# ProPrj___2026-01-03.net
KiCad netlist of a schematic drawn in EasyEDA Pro
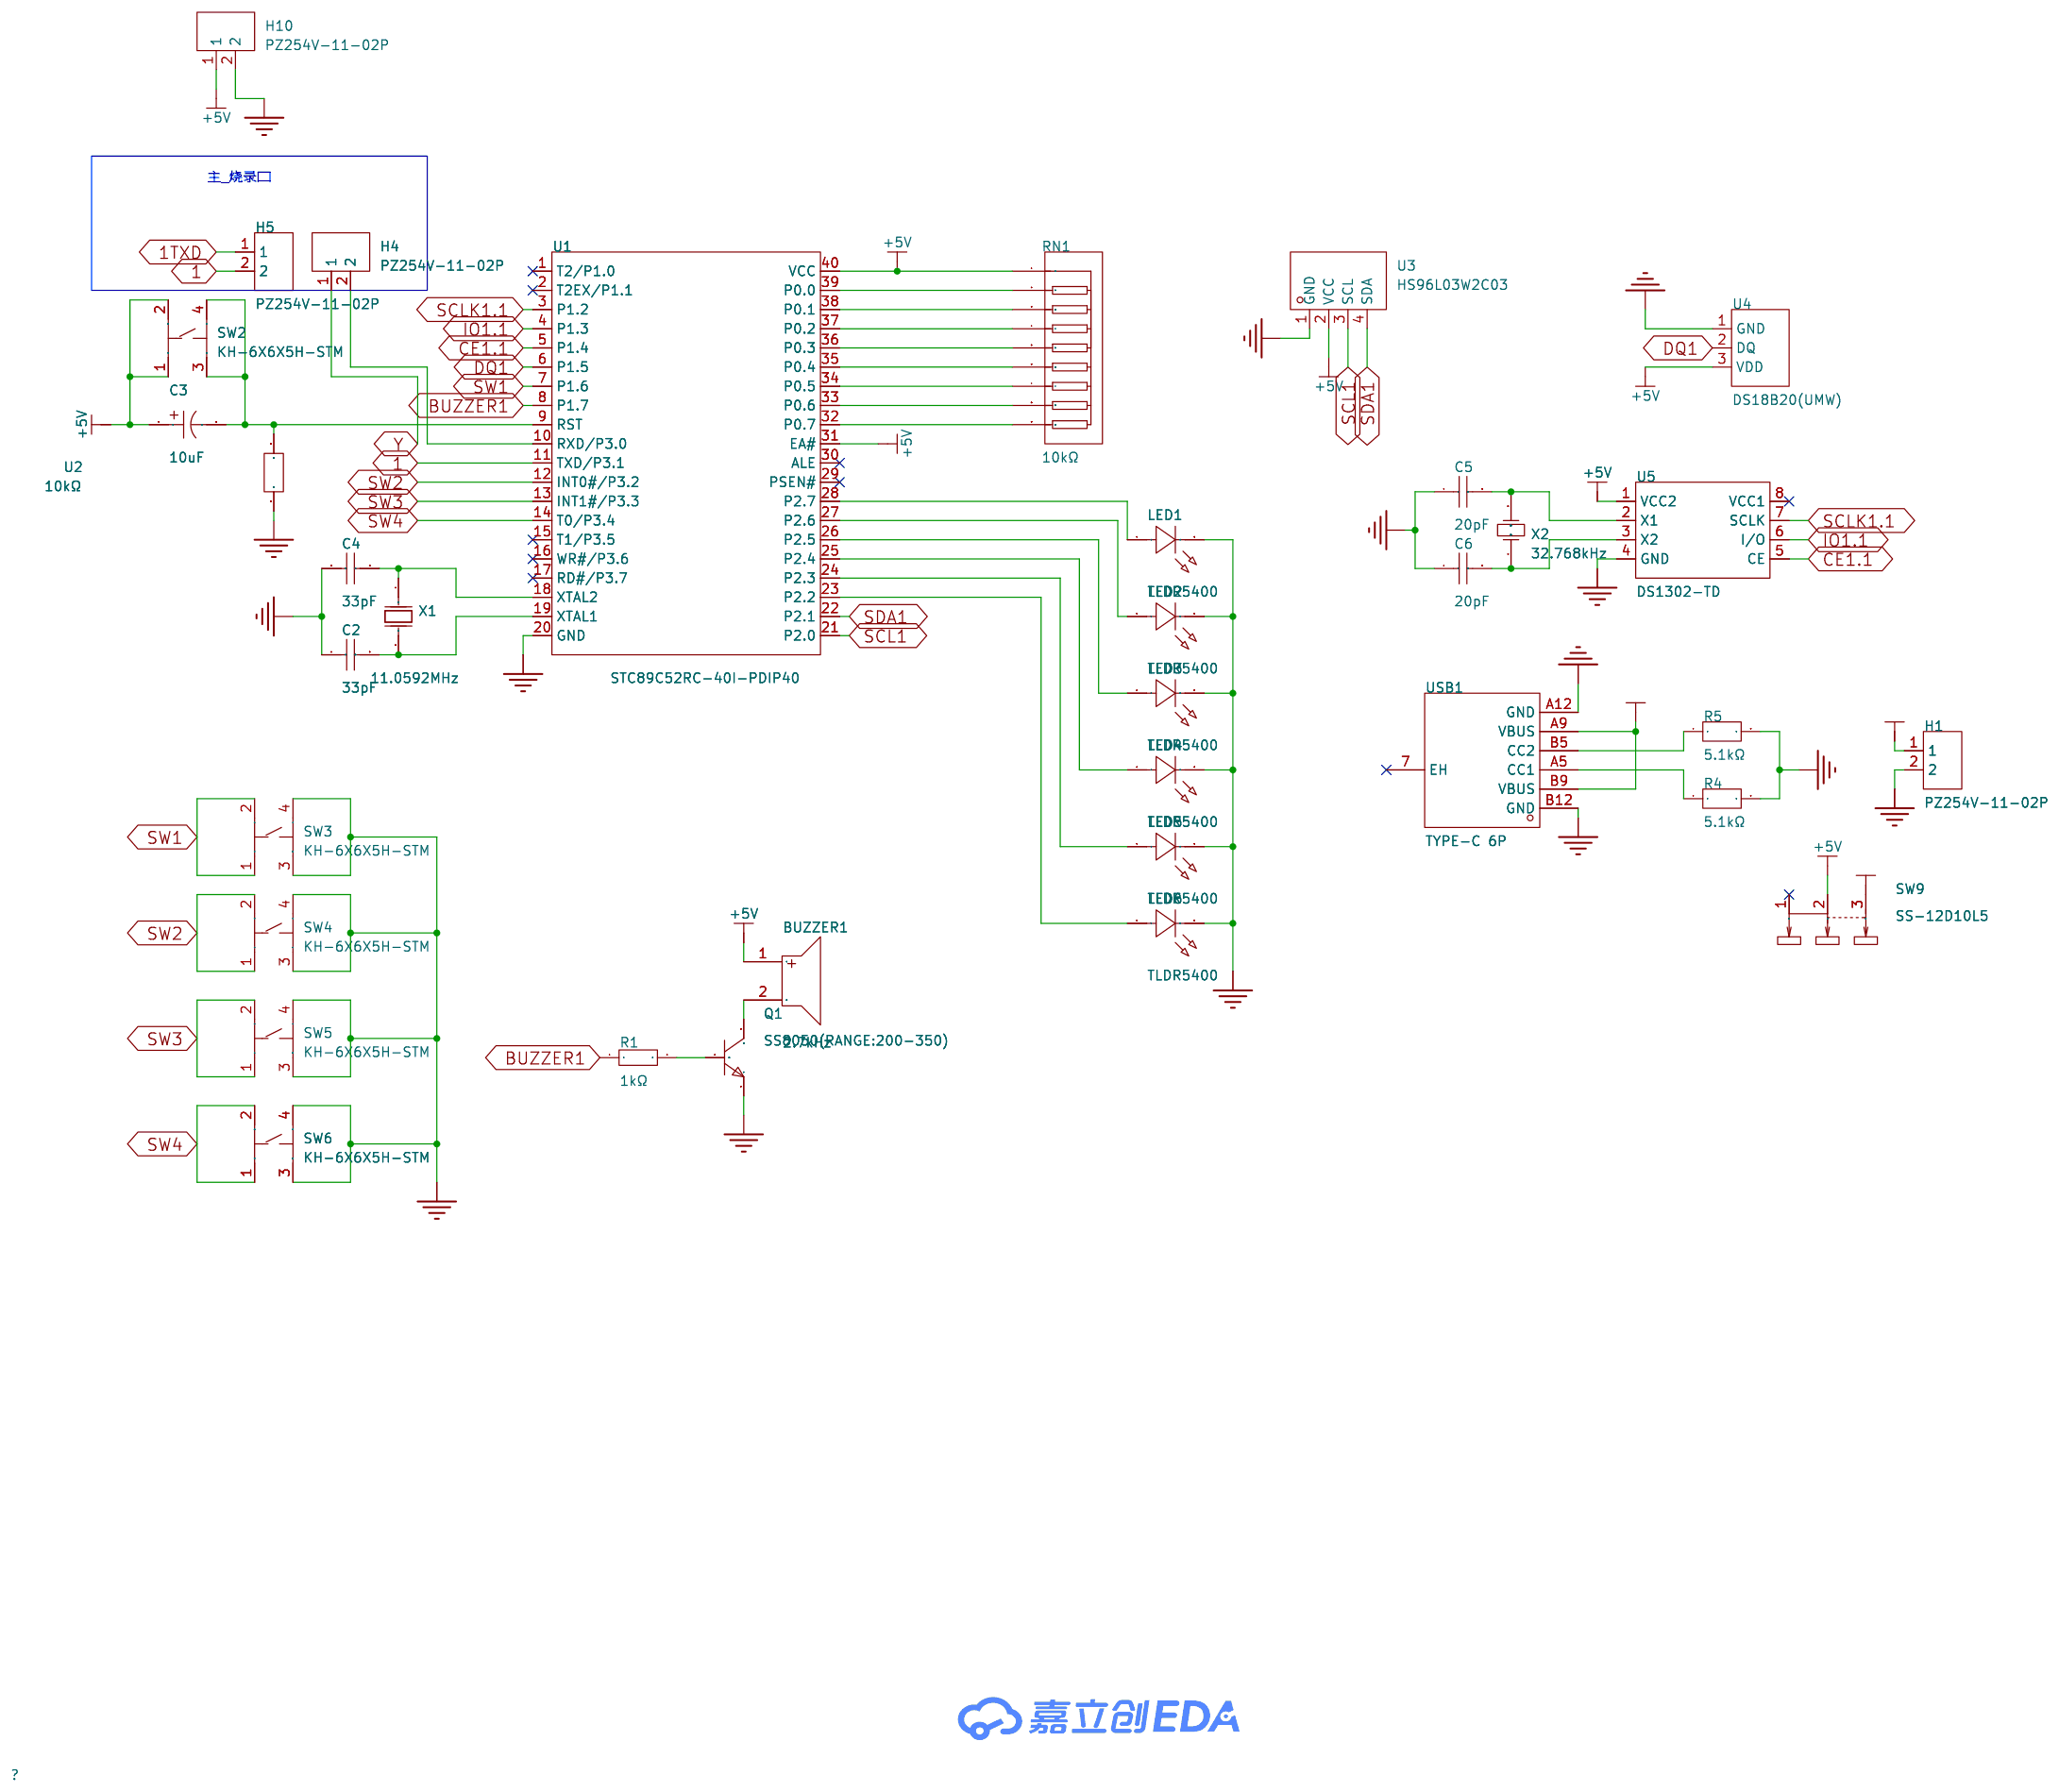
[diagram p0: 主]
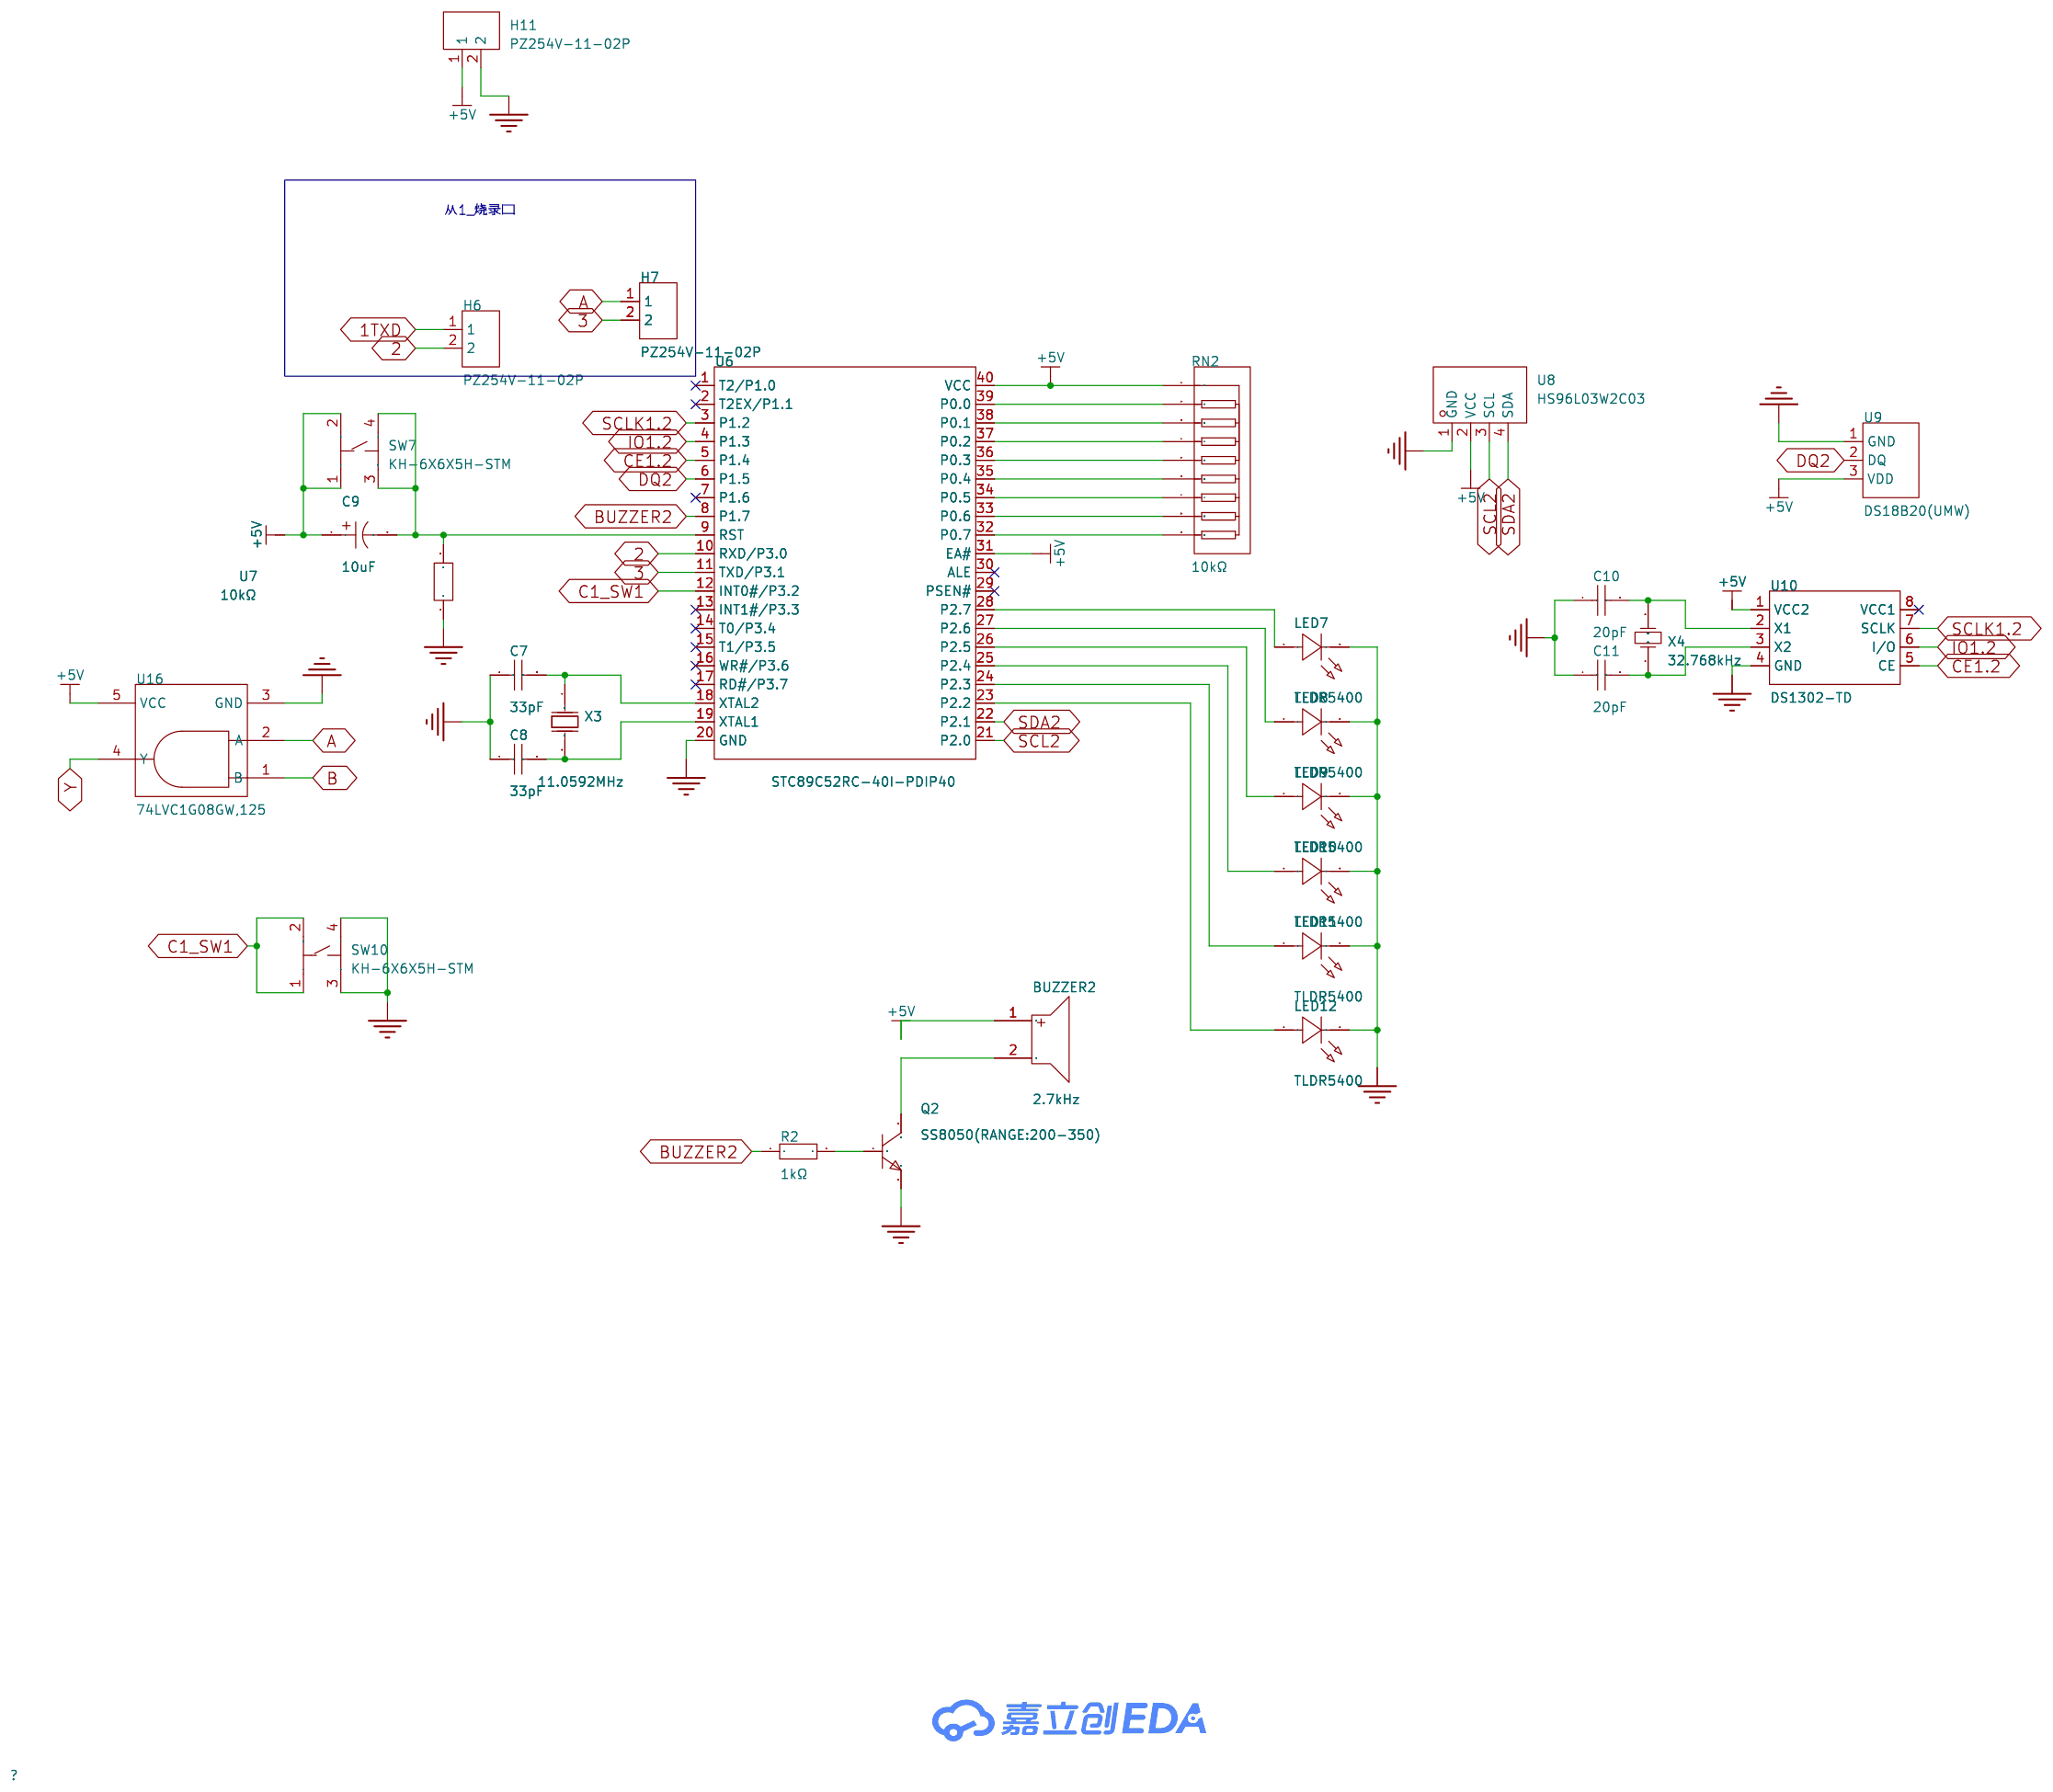
[diagram p1: 从1]
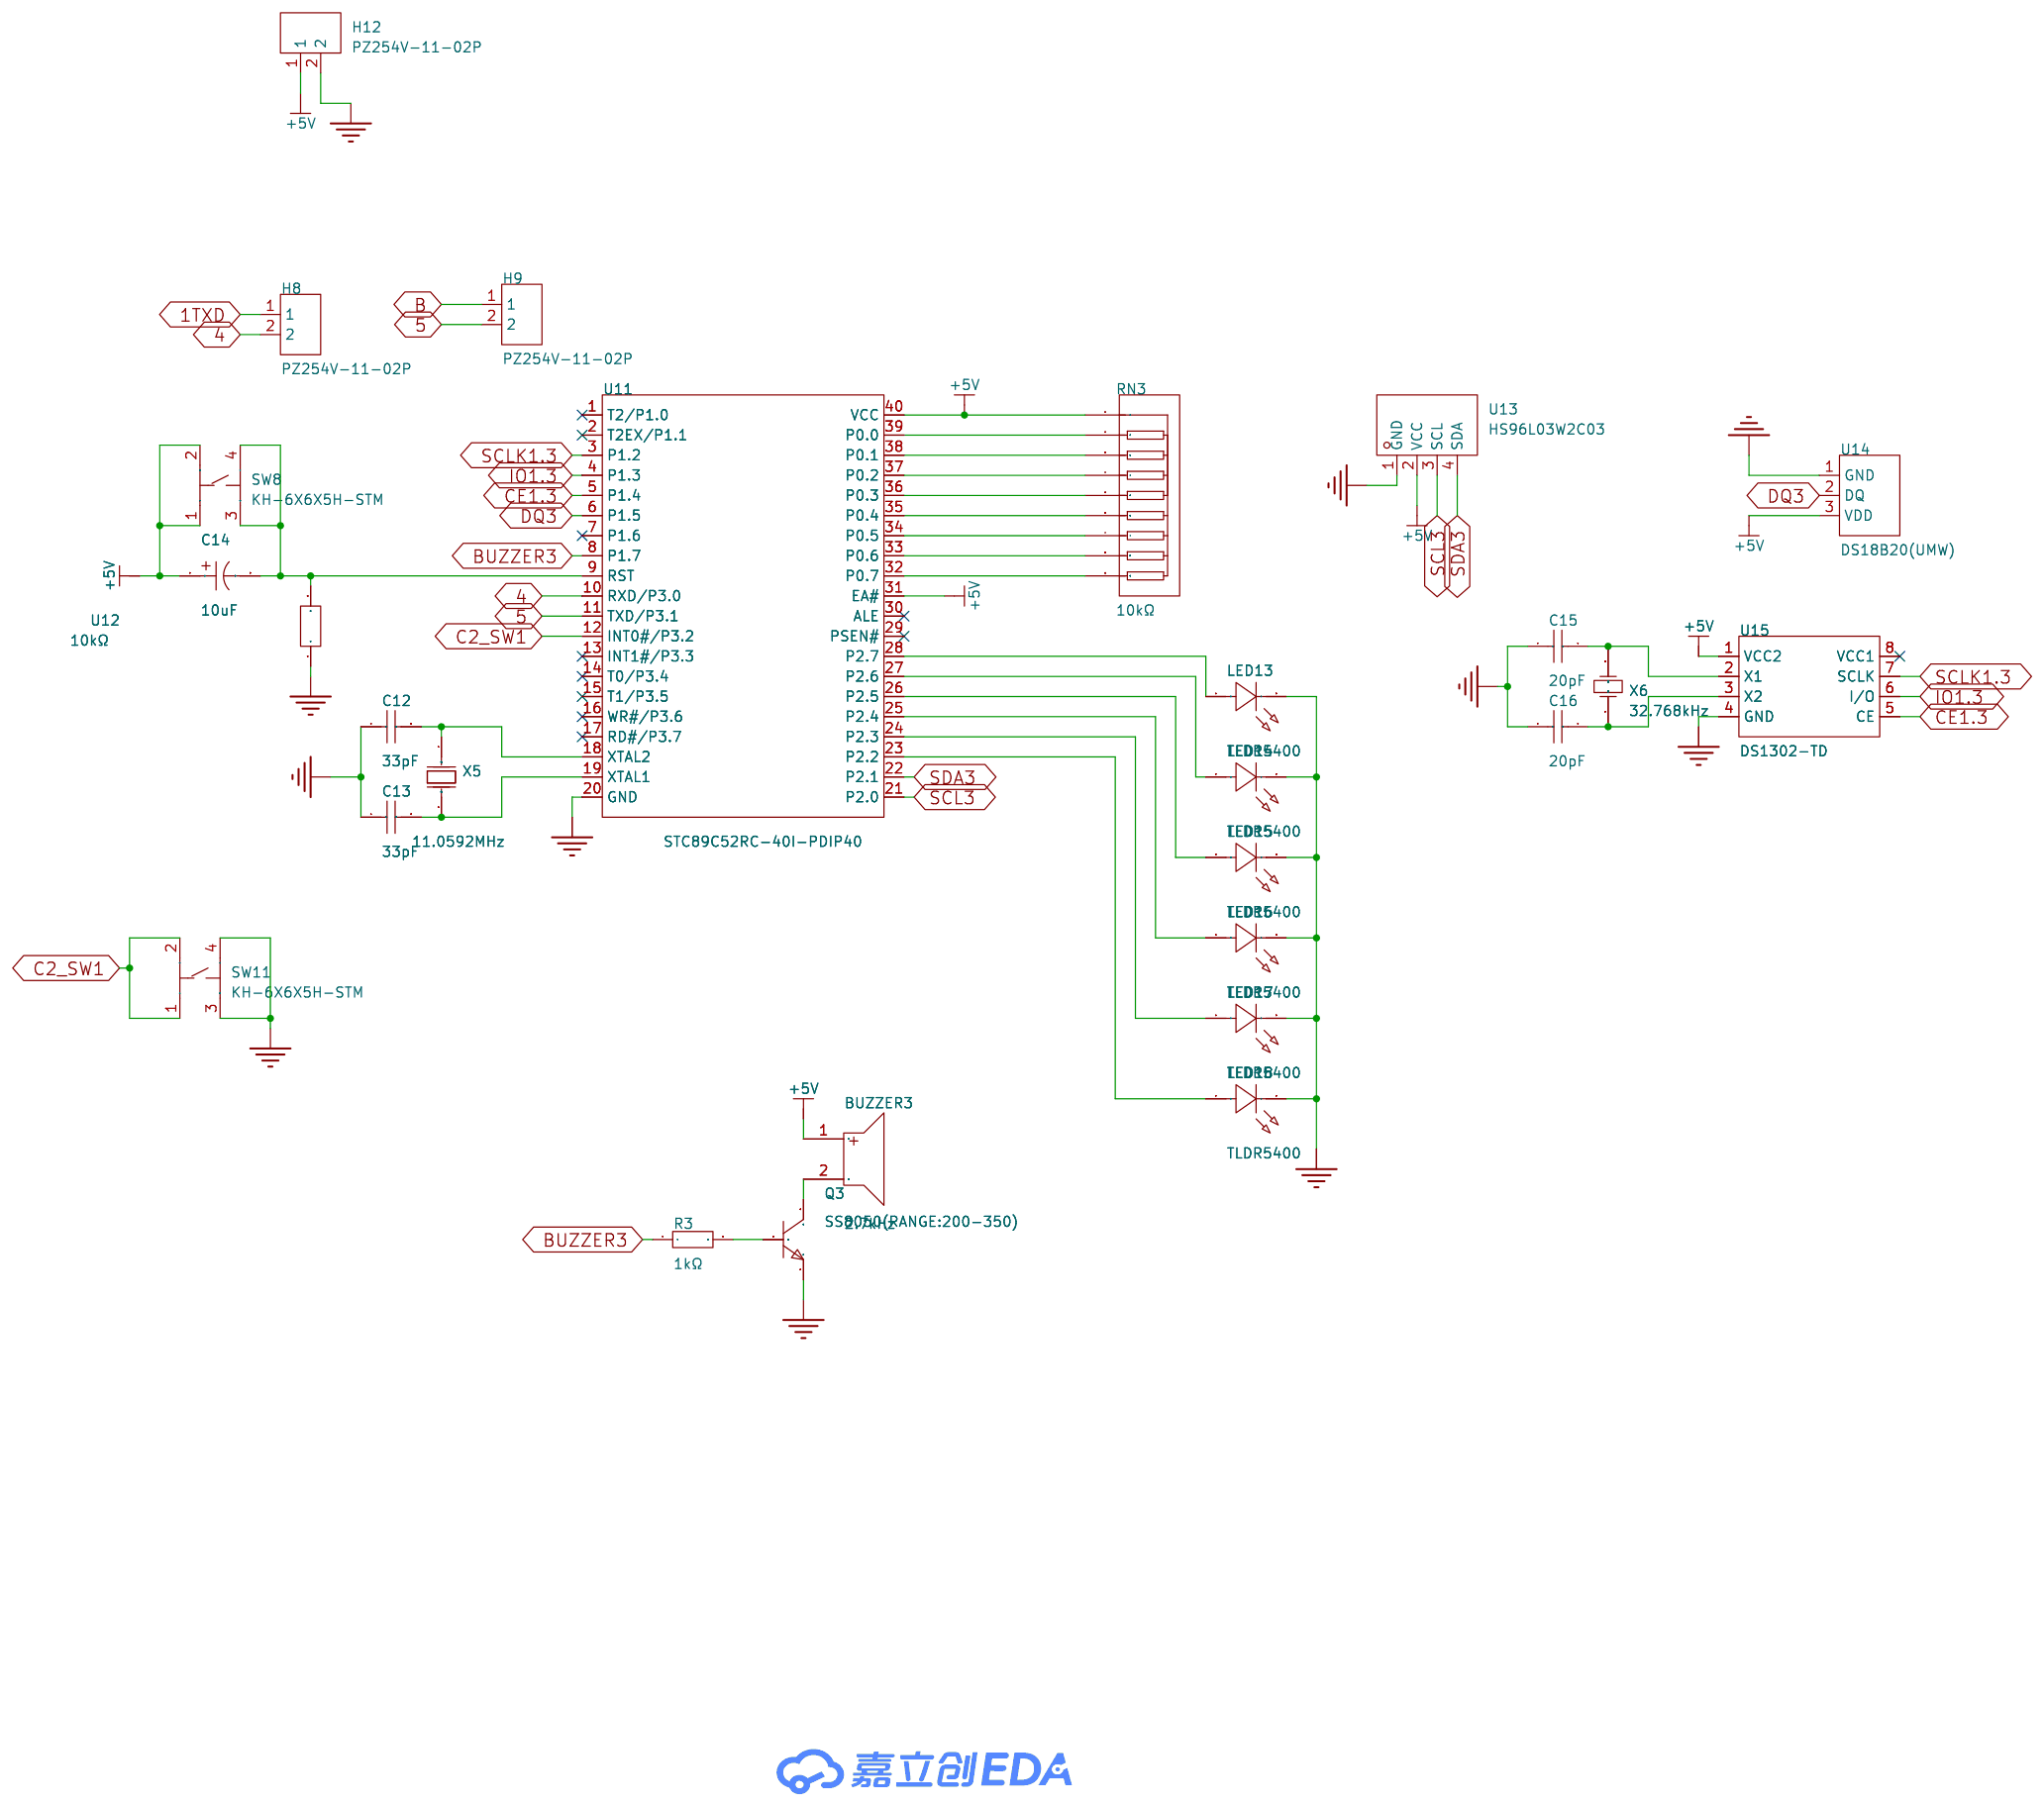
[diagram p2: 从2]

(export (version "E")
  (design (tool "Eeschema 10.0.6"))
  (components
    (comp (ref "BUZZER1")
      (value "2.7kHz")
      (footprint "easyedapro:BUZ-TH_BD9.0-P4.00-D0.6-FD")
      (description "驱动方式:无源(外部驱动);构造类型:电磁式;频率:2.7kHz;声压(SPL):85dB;")
      (fields (field (name "Manufacturer Part") "QMB-09B-03") (field (name "Manufacturer") "华能"))
      (libsource (lib "easyedapro") (part "QMB-09B-03"))
    )
    (comp (ref "C2")
      (value "33pF")
      (footprint "easyedapro:C0603")
      (description "容值:33pF;精度:±5%;额定电压:50V;温度系数:C0G;")
      (fields
        (field (name "Manufacturer Part") "CL10C330JB8NNNC")
        (field (name "Manufacturer") "SAMSUNG(三星)")
      )
      (libsource (lib "easyedapro") (part "CL10C330JB8NNNC"))
    )
    (comp (ref "C3")
      (value "10uF")
      (footprint "easyedapro:CAP-TH_BD10.0-P5.00-D0.6-FD_1")
      (description "容值:10uF;精度:±20%;额定电压:450V;纹波电流:100mA@100kHz;等效串联电阻(ESR):9.45Ω@100kHz;")
      (fields (field (name "Manufacturer Part") "ERG450V10M10x16") (field (name "Manufacturer") "JIERR(捷而瑞)"))
      (libsource (lib "easyedapro") (part "ERG450V10M10X16"))
    )
    (comp (ref "C4")
      (value "33pF")
      (footprint "easyedapro:C0603")
      (description "容值:33pF;精度:±5%;额定电压:50V;温度系数:C0G;")
      (fields
        (field (name "Manufacturer Part") "CL10C330JB8NNNC")
        (field (name "Manufacturer") "SAMSUNG(三星)")
      )
      (libsource (lib "easyedapro") (part "CL10C330JB8NNNC"))
    )
    (comp (ref "C5")
      (value "20pF")
      (footprint "easyedapro:C0603")
      (description "容值:20pF;精度:±5%;额定电压:50V;温度系数:C0G;")
      (fields
        (field (name "Manufacturer Part") "CL10C200JB8NNNC")
        (field (name "Manufacturer") "SAMSUNG(三星)")
      )
      (libsource (lib "easyedapro") (part "CL10C200JB8NNNC"))
    )
    (comp (ref "C6")
      (value "20pF")
      (footprint "easyedapro:C0603")
      (description "容值:20pF;精度:±5%;额定电压:50V;温度系数:C0G;")
      (fields
        (field (name "Manufacturer Part") "CL10C200JB8NNNC")
        (field (name "Manufacturer") "SAMSUNG(三星)")
      )
      (libsource (lib "easyedapro") (part "CL10C200JB8NNNC"))
    )
    (comp (ref "H1")
      (value "PZ254V-11-02P")
      (footprint "easyedapro:HDR-TH_2P-P2.54-V-M")
      (fields (field (name "Manufacturer") "XFCN(兴飞)"))
      (libsource (lib "easyedapro") (part "PZ254V-11-02P"))
    )
    (comp (ref "H4")
      (value "PZ254V-11-02P")
      (footprint "easyedapro:HDR-TH_2P-P2.54-V-M")
      (fields (field (name "Manufacturer") "XFCN(兴飞)"))
      (libsource (lib "easyedapro") (part "PZ254V-11-02P"))
    )
    (comp (ref "H5")
      (value "PZ254V-11-02P")
      (footprint "easyedapro:HDR-TH_2P-P2.54-V-M")
      (fields (field (name "Manufacturer") "XFCN(兴飞)"))
      (libsource (lib "easyedapro") (part "PZ254V-11-02P"))
    )
    (comp (ref "H10")
      (value "PZ254V-11-02P")
      (footprint "easyedapro:HDR-TH_2P-P2.54-V-M")
      (fields (field (name "Manufacturer") "XFCN(兴飞)"))
      (libsource (lib "easyedapro") (part "PZ254V-11-02P"))
    )
    (comp (ref "LED1")
      (value "TLDR5400")
      (footprint "easyedapro:LED-TH_BD5.8-P2.54-FD_RED")
      (fields (field (name "Manufacturer") "VISHAY(威世)"))
      (libsource (lib "easyedapro") (part "TLDR5400"))
    )
    (comp (ref "LED2")
      (value "TLDR5400")
      (footprint "easyedapro:LED-TH_BD5.8-P2.54-FD_RED")
      (fields (field (name "Manufacturer") "VISHAY(威世)"))
      (libsource (lib "easyedapro") (part "TLDR5400"))
    )
    (comp (ref "LED3")
      (value "TLDR5400")
      (footprint "easyedapro:LED-TH_BD5.8-P2.54-FD_RED")
      (fields (field (name "Manufacturer") "VISHAY(威世)"))
      (libsource (lib "easyedapro") (part "TLDR5400"))
    )
    (comp (ref "LED4")
      (value "TLDR5400")
      (footprint "easyedapro:LED-TH_BD5.8-P2.54-FD_RED")
      (fields (field (name "Manufacturer") "VISHAY(威世)"))
      (libsource (lib "easyedapro") (part "TLDR5400"))
    )
    (comp (ref "LED5")
      (value "TLDR5400")
      (footprint "easyedapro:LED-TH_BD5.8-P2.54-FD_RED")
      (fields (field (name "Manufacturer") "VISHAY(威世)"))
      (libsource (lib "easyedapro") (part "TLDR5400"))
    )
    (comp (ref "LED6")
      (value "TLDR5400")
      (footprint "easyedapro:LED-TH_BD5.8-P2.54-FD_RED")
      (fields (field (name "Manufacturer") "VISHAY(威世)"))
      (libsource (lib "easyedapro") (part "TLDR5400"))
    )
    (comp (ref "Q1")
      (value "SS8050(RANGE:200-350)")
      (footprint "easyedapro:SOT-23-3_L2.9-W1.3-P1.90-LS2.4-BR")
      (description "晶体管类型:NPN;集电极电流(Ic):1.5A;集射极击穿电压(Vceo):25V;耗散功率(Pd):300mW;直流电流增益(hFE):200@800mA,1V;")
      (fields (field (name "Manufacturer") "CJ(江苏长电/长晶)"))
      (libsource (lib "easyedapro") (part "SS8050_C2150"))
    )
    (comp (ref "R1")
      (value "1kΩ")
      (footprint "easyedapro:RES-TH_BD2.5-L6.5-P10.50-D0.6")
      (description "电阻类型:金属膜电阻;阻值:1kΩ;精度:±1%;功率:250mW;温度系数:±50ppm/°C;")
      (fields
        (field (name "Manufacturer Part") "MFR0W4F1001A50")
        (field (name "Manufacturer") "UNI-ROYAL(厚声)")
      )
      (libsource (lib "easyedapro") (part "MFR0W4F1001A50"))
    )
    (comp (ref "R4")
      (value "5.1kΩ")
      (footprint "easyedapro:RES-TH_BD2.3-L6.5-P10.50-D0.5")
      (description "电阻类型:金属膜电阻;阻值:5.1kΩ;精度:±1%;功率:250mW;温度系数:±200ppm/°C;")
      (fields (field (name "Manufacturer Part") "MF1/4W-5.1KΩ±1%T52") (field (name "Manufacturer") "华星机电"))
      (libsource (lib "easyedapro") (part "MF1/4W-5.1KΩ±1%T52"))
    )
    (comp (ref "R5")
      (value "5.1kΩ")
      (footprint "easyedapro:RES-TH_BD2.3-L6.5-P10.50-D0.5")
      (description "电阻类型:金属膜电阻;阻值:5.1kΩ;精度:±1%;功率:250mW;温度系数:±200ppm/°C;")
      (fields (field (name "Manufacturer Part") "MF1/4W-5.1KΩ±1%T52") (field (name "Manufacturer") "华星机电"))
      (libsource (lib "easyedapro") (part "MF1/4W-5.1KΩ±1%T52"))
    )
    (comp (ref "RN1")
      (value "10kΩ")
      (footprint "easyedapro:RES-ARRAY-TH_9P-P2.54-D1.0")
      (description "电阻器数:8;阻值:10kΩ;精度:±5%;单个元件功率:125mW;温度系数:±100ppm/°C;")
      (fields (field (name "Manufacturer Part") "A09-103JP") (field (name "Manufacturer") "FH(风华)"))
      (libsource (lib "easyedapro") (part "A09-103JP"))
    )
    (comp (ref "SW2")
      (value "KH-6X6X5H-STM")
      (footprint "easyedapro:SW-SMD_4P-L6.0-W6.0-P4.50-LS9.0_H5.0")
      (description "电路结构:单刀单掷;按钮形状:圆形按钮;安装方式:立贴;开关长度:6mm;开关宽度:6mm;开关高度:5mm;带支架:不带支架;触点电流:50mA;额定电压:12V;工作寿命:8万次;")
      (fields (field (name "Manufacturer") "kinghelm(金航标)"))
      (libsource (lib "easyedapro") (part "KH-6X6X5H-STM"))
    )
    (comp (ref "SW3")
      (value "KH-6X6X5H-STM")
      (footprint "easyedapro:SW-SMD_4P-L6.0-W6.0-P4.50-LS9.0_H5.0")
      (description "电路结构:单刀单掷;按钮形状:圆形按钮;安装方式:立贴;开关长度:6mm;开关宽度:6mm;开关高度:5mm;带支架:不带支架;触点电流:50mA;额定电压:12V;工作寿命:8万次;")
      (fields (field (name "Manufacturer") "kinghelm(金航标)"))
      (libsource (lib "easyedapro") (part "KH-6X6X5H-STM"))
    )
    (comp (ref "SW4")
      (value "KH-6X6X5H-STM")
      (footprint "easyedapro:SW-SMD_4P-L6.0-W6.0-P4.50-LS9.0_H5.0")
      (description "电路结构:单刀单掷;按钮形状:圆形按钮;安装方式:立贴;开关长度:6mm;开关宽度:6mm;开关高度:5mm;带支架:不带支架;触点电流:50mA;额定电压:12V;工作寿命:8万次;")
      (fields (field (name "Manufacturer") "kinghelm(金航标)"))
      (libsource (lib "easyedapro") (part "KH-6X6X5H-STM"))
    )
    (comp (ref "SW5")
      (value "KH-6X6X5H-STM")
      (footprint "easyedapro:SW-SMD_4P-L6.0-W6.0-P4.50-LS9.0_H5.0")
      (description "电路结构:单刀单掷;按钮形状:圆形按钮;安装方式:立贴;开关长度:6mm;开关宽度:6mm;开关高度:5mm;带支架:不带支架;触点电流:50mA;额定电压:12V;工作寿命:8万次;")
      (fields (field (name "Manufacturer") "kinghelm(金航标)"))
      (libsource (lib "easyedapro") (part "KH-6X6X5H-STM"))
    )
    (comp (ref "SW6")
      (value "KH-6X6X5H-STM")
      (footprint "easyedapro:SW-SMD_4P-L6.0-W6.0-P4.50-LS9.0_H5.0")
      (description "电路结构:单刀单掷;按钮形状:圆形按钮;安装方式:立贴;开关长度:6mm;开关宽度:6mm;开关高度:5mm;带支架:不带支架;触点电流:50mA;额定电压:12V;工作寿命:8万次;")
      (fields (field (name "Manufacturer") "kinghelm(金航标)"))
      (libsource (lib "easyedapro") (part "KH-6X6X5H-STM"))
    )
    (comp (ref "SW9")
      (value "SS-12D10L5")
      (footprint "easyedapro:SW-TH_SS-12D10L5")
      (description "电路结构:单刀双掷;安装方式:直插;开关颜色:黑色;额定电流:3A;额定电压:125V;工作寿命:1万次;")
      (fields (field (name "Manufacturer") "XKB Connection(中国星坤)"))
      (libsource (lib "easyedapro") (part "SS-12D10L5"))
    )
    (comp (ref "U1")
      (value "STC89C52RC-40I-PDIP40")
      (footprint "easyedapro:DIP-40_L52.0-W13.7-P2.54-LS15.2-BL")
      (description "CPU内核:51家族;CPU最大主频:-;")
      (fields (field (name "Manufacturer") "STC"))
      (libsource (lib "easyedapro") (part "STC89C52RC-40I"))
    )
    (comp (ref "U2")
      (value "10kΩ")
      (footprint "easyedapro:RES-TH_BD2.3-L6.3-P10.30-D0.6")
      (description "电阻类型:金属膜电阻;阻值:10kΩ;精度:±1%;功率:600mW;温度系数:±50ppm/°C;")
      (fields
        (field (name "Manufacturer Part") "LR1F10K")
        (field (name "Manufacturer") "TE Connectivity(泰科电子)")
      )
      (libsource (lib "easyedapro") (part "LR1F10K"))
    )
    (comp (ref "U3")
      (value "HS96L03W2C03")
      (footprint "easyedapro:OLED-TH_L27.8-W27.2-P2.54_C9900033791")
      (description "主控芯片:SSD1315;接口类型:I2C;尺寸(inch):0.96;像素分辨率:128x64;")
      (fields (field (name "Manufacturer") "HS(汉昇)"))
      (libsource (lib "easyedapro") (part "HS96L03W2C03"))
    )
    (comp (ref "U4")
      (value "DS18B20(UMW)")
      (footprint "easyedapro:TO-92-3_L4.9-W3.7-P1.27-L")
      (description "温度范围:-55°C~+125°C;精度:±0.4°C;接口类型:-;")
      (fields (field (name "Manufacturer") "UMW(友台半导体)"))
      (libsource (lib "easyedapro") (part "DS18B20"))
    )
    (comp (ref "U5")
      (value "DS1302-TD")
      (footprint "easyedapro:SOP-8_L4.9-W3.9-P1.27-LS6.0-BL")
      (description "接口类型:SPI;晶振:外置;闹钟输出:有;")
      (fields (field (name "Manufacturer") "TDSEMIC(拓电半导体)"))
      (libsource (lib "easyedapro") (part "DS1302-TD"))
    )
    (comp (ref "USB1")
      (value "TYPE-C 6P")
      (footprint "easyedapro:TYPE-C-SMD_TYPE-C-6P")
      (description "连接器类型:Type-C;标准:USB 3.1;公母:母;安装方式:卧贴;触点数量:6P;端口数量:1;额定电流 - 电源:5A;工作温度范围:-40°C~+85°C;")
      (fields (field (name "Manufacturer") "SHOU HAN(首韩)"))
      (libsource (lib "easyedapro") (part "TYPE-C 6P"))
    )
    (comp (ref "X1")
      (value "11.0592MHz")
      (footprint "easyedapro:HC-49US_L11.5-W4.5-P4.88")
      (description "晶振类型:直插晶振;频率:11.0592MHz;常温频差:±20ppm;负载电容:20pF;频率稳定度:±30ppm;")
      (fields
        (field (name "Manufacturer Part") "X49SD110592MSD2SC")
        (field (name "Manufacturer") "YXC(扬兴晶振)")
      )
      (libsource (lib "easyedapro") (part "X49SD110592MSD2SC"))
    )
    (comp (ref "X2")
      (value "32.768kHz")
      (footprint "easyedapro:OSC-TH_BD3.1-P0.8-D0.3")
      (description "晶振类型:直插晶振;频率:32.768kHz;常温频差:±10ppm;负载电容:12.5pF;频率稳定度:±20ppm;")
      (fields (field (name "Manufacturer Part") "X308032768KGB2SC") (field (name "Manufacturer") "YXC(扬兴晶振)"))
      (libsource (lib "easyedapro") (part "X308032768KGB2SC"))
    )
    (comp (ref "BUZZER2")
      (value "2.7kHz")
      (footprint "easyedapro:BUZ-TH_BD9.0-P4.00-D0.6-FD")
      (description "驱动方式:无源(外部驱动);构造类型:电磁式;频率:2.7kHz;声压(SPL):85dB;")
      (fields (field (name "Manufacturer Part") "QMB-09B-03") (field (name "Manufacturer") "华能"))
      (libsource (lib "easyedapro") (part "QMB-09B-03"))
    )
    (comp (ref "C7")
      (value "33pF")
      (footprint "easyedapro:C0603")
      (description "容值:33pF;精度:±5%;额定电压:50V;温度系数:C0G;")
      (fields
        (field (name "Manufacturer Part") "CL10C330JB8NNNC")
        (field (name "Manufacturer") "SAMSUNG(三星)")
      )
      (libsource (lib "easyedapro") (part "CL10C330JB8NNNC"))
    )
    (comp (ref "C8")
      (value "33pF")
      (footprint "easyedapro:C0603")
      (description "容值:33pF;精度:±5%;额定电压:50V;温度系数:C0G;")
      (fields
        (field (name "Manufacturer Part") "CL10C330JB8NNNC")
        (field (name "Manufacturer") "SAMSUNG(三星)")
      )
      (libsource (lib "easyedapro") (part "CL10C330JB8NNNC"))
    )
    (comp (ref "C9")
      (value "10uF")
      (footprint "easyedapro:CAP-TH_BD10.0-P5.00-D0.6-FD_1")
      (description "容值:10uF;精度:±20%;额定电压:450V;纹波电流:100mA@100kHz;等效串联电阻(ESR):9.45Ω@100kHz;")
      (fields (field (name "Manufacturer Part") "ERG450V10M10x16") (field (name "Manufacturer") "JIERR(捷而瑞)"))
      (libsource (lib "easyedapro") (part "ERG450V10M10X16"))
    )
    (comp (ref "C10")
      (value "20pF")
      (footprint "easyedapro:C0603")
      (description "容值:20pF;精度:±5%;额定电压:50V;温度系数:C0G;")
      (fields
        (field (name "Manufacturer Part") "CL10C200JB8NNNC")
        (field (name "Manufacturer") "SAMSUNG(三星)")
      )
      (libsource (lib "easyedapro") (part "CL10C200JB8NNNC"))
    )
    (comp (ref "C11")
      (value "20pF")
      (footprint "easyedapro:C0603")
      (description "容值:20pF;精度:±5%;额定电压:50V;温度系数:C0G;")
      (fields
        (field (name "Manufacturer Part") "CL10C200JB8NNNC")
        (field (name "Manufacturer") "SAMSUNG(三星)")
      )
      (libsource (lib "easyedapro") (part "CL10C200JB8NNNC"))
    )
    (comp (ref "H6")
      (value "PZ254V-11-02P")
      (footprint "easyedapro:HDR-TH_2P-P2.54-V-M")
      (fields (field (name "Manufacturer") "XFCN(兴飞)"))
      (libsource (lib "easyedapro") (part "PZ254V-11-02P"))
    )
    (comp (ref "H7")
      (value "PZ254V-11-02P")
      (footprint "easyedapro:HDR-TH_2P-P2.54-V-M")
      (fields (field (name "Manufacturer") "XFCN(兴飞)"))
      (libsource (lib "easyedapro") (part "PZ254V-11-02P"))
    )
    (comp (ref "H11")
      (value "PZ254V-11-02P")
      (footprint "easyedapro:HDR-TH_2P-P2.54-V-M")
      (fields (field (name "Manufacturer") "XFCN(兴飞)"))
      (libsource (lib "easyedapro") (part "PZ254V-11-02P"))
    )
    (comp (ref "LED7")
      (value "TLDR5400")
      (footprint "easyedapro:LED-TH_BD5.8-P2.54-FD_RED")
      (fields (field (name "Manufacturer") "VISHAY(威世)"))
      (libsource (lib "easyedapro") (part "TLDR5400"))
    )
    (comp (ref "LED8")
      (value "TLDR5400")
      (footprint "easyedapro:LED-TH_BD5.8-P2.54-FD_RED")
      (fields (field (name "Manufacturer") "VISHAY(威世)"))
      (libsource (lib "easyedapro") (part "TLDR5400"))
    )
    (comp (ref "LED9")
      (value "TLDR5400")
      (footprint "easyedapro:LED-TH_BD5.8-P2.54-FD_RED")
      (fields (field (name "Manufacturer") "VISHAY(威世)"))
      (libsource (lib "easyedapro") (part "TLDR5400"))
    )
    (comp (ref "LED10")
      (value "TLDR5400")
      (footprint "easyedapro:LED-TH_BD5.8-P2.54-FD_RED")
      (fields (field (name "Manufacturer") "VISHAY(威世)"))
      (libsource (lib "easyedapro") (part "TLDR5400"))
    )
    (comp (ref "LED11")
      (value "TLDR5400")
      (footprint "easyedapro:LED-TH_BD5.8-P2.54-FD_RED")
      (fields (field (name "Manufacturer") "VISHAY(威世)"))
      (libsource (lib "easyedapro") (part "TLDR5400"))
    )
    (comp (ref "LED12")
      (value "TLDR5400")
      (footprint "easyedapro:LED-TH_BD5.8-P2.54-FD_RED")
      (fields (field (name "Manufacturer") "VISHAY(威世)"))
      (libsource (lib "easyedapro") (part "TLDR5400"))
    )
    (comp (ref "Q2")
      (value "SS8050(RANGE:200-350)")
      (footprint "easyedapro:SOT-23-3_L2.9-W1.3-P1.90-LS2.4-BR")
      (description "晶体管类型:NPN;集电极电流(Ic):1.5A;集射极击穿电压(Vceo):25V;耗散功率(Pd):300mW;直流电流增益(hFE):200@800mA,1V;")
      (fields (field (name "Manufacturer") "CJ(江苏长电/长晶)"))
      (libsource (lib "easyedapro") (part "SS8050_C2150"))
    )
    (comp (ref "R2")
      (value "1kΩ")
      (footprint "easyedapro:RES-TH_BD2.5-L6.5-P10.50-D0.6")
      (description "电阻类型:金属膜电阻;阻值:1kΩ;精度:±1%;功率:250mW;温度系数:±50ppm/°C;")
      (fields
        (field (name "Manufacturer Part") "MFR0W4F1001A50")
        (field (name "Manufacturer") "UNI-ROYAL(厚声)")
      )
      (libsource (lib "easyedapro") (part "MFR0W4F1001A50"))
    )
    (comp (ref "RN2")
      (value "10kΩ")
      (footprint "easyedapro:RES-ARRAY-TH_9P-P2.54-D1.0")
      (description "电阻器数:8;阻值:10kΩ;精度:±5%;单个元件功率:125mW;温度系数:±100ppm/°C;")
      (fields (field (name "Manufacturer Part") "A09-103JP") (field (name "Manufacturer") "FH(风华)"))
      (libsource (lib "easyedapro") (part "A09-103JP"))
    )
    (comp (ref "SW7")
      (value "KH-6X6X5H-STM")
      (footprint "easyedapro:SW-SMD_4P-L6.0-W6.0-P4.50-LS9.0_H5.0")
      (description "电路结构:单刀单掷;按钮形状:圆形按钮;安装方式:立贴;开关长度:6mm;开关宽度:6mm;开关高度:5mm;带支架:不带支架;触点电流:50mA;额定电压:12V;工作寿命:8万次;")
      (fields (field (name "Manufacturer") "kinghelm(金航标)"))
      (libsource (lib "easyedapro") (part "KH-6X6X5H-STM"))
    )
    (comp (ref "SW10")
      (value "KH-6X6X5H-STM")
      (footprint "easyedapro:SW-SMD_4P-L6.0-W6.0-P4.50-LS9.0_H5.0")
      (description "电路结构:单刀单掷;按钮形状:圆形按钮;安装方式:立贴;开关长度:6mm;开关宽度:6mm;开关高度:5mm;带支架:不带支架;触点电流:50mA;额定电压:12V;工作寿命:8万次;")
      (fields (field (name "Manufacturer") "kinghelm(金航标)"))
      (libsource (lib "easyedapro") (part "KH-6X6X5H-STM"))
    )
    (comp (ref "U6")
      (value "STC89C52RC-40I-PDIP40")
      (footprint "easyedapro:DIP-40_L52.0-W13.7-P2.54-LS15.2-BL")
      (description "CPU内核:51家族;CPU最大主频:-;")
      (fields (field (name "Manufacturer") "STC"))
      (libsource (lib "easyedapro") (part "STC89C52RC-40I"))
    )
    (comp (ref "U7")
      (value "10kΩ")
      (footprint "easyedapro:RES-TH_BD2.3-L6.3-P10.30-D0.6")
      (description "电阻类型:金属膜电阻;阻值:10kΩ;精度:±1%;功率:600mW;温度系数:±50ppm/°C;")
      (fields
        (field (name "Manufacturer Part") "LR1F10K")
        (field (name "Manufacturer") "TE Connectivity(泰科电子)")
      )
      (libsource (lib "easyedapro") (part "LR1F10K"))
    )
    (comp (ref "U8")
      (value "HS96L03W2C03")
      (footprint "easyedapro:OLED-TH_L27.8-W27.2-P2.54_C9900033791")
      (description "主控芯片:SSD1315;接口类型:I2C;尺寸(inch):0.96;像素分辨率:128x64;")
      (fields (field (name "Manufacturer") "HS(汉昇)"))
      (libsource (lib "easyedapro") (part "HS96L03W2C03"))
    )
    (comp (ref "U9")
      (value "DS18B20(UMW)")
      (footprint "easyedapro:TO-92-3_L4.9-W3.7-P1.27-L")
      (description "温度范围:-55°C~+125°C;精度:±0.4°C;接口类型:-;")
      (fields (field (name "Manufacturer") "UMW(友台半导体)"))
      (libsource (lib "easyedapro") (part "DS18B20"))
    )
    (comp (ref "U10")
      (value "DS1302-TD")
      (footprint "easyedapro:SOP-8_L4.9-W3.9-P1.27-LS6.0-BL")
      (description "接口类型:SPI;晶振:外置;闹钟输出:有;")
      (fields (field (name "Manufacturer") "TDSEMIC(拓电半导体)"))
      (libsource (lib "easyedapro") (part "DS1302-TD"))
    )
    (comp (ref "U16")
      (value "74LVC1G08GW,125")
      (footprint "easyedapro:SOT-353_L2.1-W1.3-P0.65-LS2.3-BR")
      (description "逻辑类型:与门;通道数:1;电源电压:1.65V~5.5V;静态电流(最大值):4uA;最大传播延迟:4ns@5V,50pF;")
      (fields (field (name "Manufacturer") "Nexperia(安世)"))
      (libsource (lib "easyedapro") (part "74LVC1G08GW,125"))
    )
    (comp (ref "X3")
      (value "11.0592MHz")
      (footprint "easyedapro:HC-49US_L11.5-W4.5-P4.88")
      (description "晶振类型:直插晶振;频率:11.0592MHz;常温频差:±20ppm;负载电容:20pF;频率稳定度:±30ppm;")
      (fields
        (field (name "Manufacturer Part") "X49SD110592MSD2SC")
        (field (name "Manufacturer") "YXC(扬兴晶振)")
      )
      (libsource (lib "easyedapro") (part "X49SD110592MSD2SC"))
    )
    (comp (ref "X4")
      (value "32.768kHz")
      (footprint "easyedapro:OSC-TH_BD3.1-P0.8-D0.3")
      (description "晶振类型:直插晶振;频率:32.768kHz;常温频差:±10ppm;负载电容:12.5pF;频率稳定度:±20ppm;")
      (fields (field (name "Manufacturer Part") "X308032768KGB2SC") (field (name "Manufacturer") "YXC(扬兴晶振)"))
      (libsource (lib "easyedapro") (part "X308032768KGB2SC"))
    )
    (comp (ref "BUZZER3")
      (value "2.7kHz")
      (footprint "easyedapro:BUZ-TH_BD9.0-P4.00-D0.6-FD")
      (description "驱动方式:无源(外部驱动);构造类型:电磁式;频率:2.7kHz;声压(SPL):85dB;")
      (fields (field (name "Manufacturer Part") "QMB-09B-03") (field (name "Manufacturer") "华能"))
      (libsource (lib "easyedapro") (part "QMB-09B-03"))
    )
    (comp (ref "C12")
      (value "33pF")
      (footprint "easyedapro:C0603")
      (description "容值:33pF;精度:±5%;额定电压:50V;温度系数:C0G;")
      (fields
        (field (name "Manufacturer Part") "CL10C330JB8NNNC")
        (field (name "Manufacturer") "SAMSUNG(三星)")
      )
      (libsource (lib "easyedapro") (part "CL10C330JB8NNNC"))
    )
    (comp (ref "C13")
      (value "33pF")
      (footprint "easyedapro:C0603")
      (description "容值:33pF;精度:±5%;额定电压:50V;温度系数:C0G;")
      (fields
        (field (name "Manufacturer Part") "CL10C330JB8NNNC")
        (field (name "Manufacturer") "SAMSUNG(三星)")
      )
      (libsource (lib "easyedapro") (part "CL10C330JB8NNNC"))
    )
    (comp (ref "C14")
      (value "10uF")
      (footprint "easyedapro:CAP-TH_BD10.0-P5.00-D0.6-FD_1")
      (description "容值:10uF;精度:±20%;额定电压:450V;纹波电流:100mA@100kHz;等效串联电阻(ESR):9.45Ω@100kHz;")
      (fields (field (name "Manufacturer Part") "ERG450V10M10x16") (field (name "Manufacturer") "JIERR(捷而瑞)"))
      (libsource (lib "easyedapro") (part "ERG450V10M10X16"))
    )
    (comp (ref "C15")
      (value "20pF")
      (footprint "easyedapro:C0603")
      (description "容值:20pF;精度:±5%;额定电压:50V;温度系数:C0G;")
      (fields
        (field (name "Manufacturer Part") "CL10C200JB8NNNC")
        (field (name "Manufacturer") "SAMSUNG(三星)")
      )
      (libsource (lib "easyedapro") (part "CL10C200JB8NNNC"))
    )
    (comp (ref "C16")
      (value "20pF")
      (footprint "easyedapro:C0603")
      (description "容值:20pF;精度:±5%;额定电压:50V;温度系数:C0G;")
      (fields
        (field (name "Manufacturer Part") "CL10C200JB8NNNC")
        (field (name "Manufacturer") "SAMSUNG(三星)")
      )
      (libsource (lib "easyedapro") (part "CL10C200JB8NNNC"))
    )
    (comp (ref "H8")
      (value "PZ254V-11-02P")
      (footprint "easyedapro:HDR-TH_2P-P2.54-V-M")
      (fields (field (name "Manufacturer") "XFCN(兴飞)"))
      (libsource (lib "easyedapro") (part "PZ254V-11-02P"))
    )
    (comp (ref "H9")
      (value "PZ254V-11-02P")
      (footprint "easyedapro:HDR-TH_2P-P2.54-V-M")
      (fields (field (name "Manufacturer") "XFCN(兴飞)"))
      (libsource (lib "easyedapro") (part "PZ254V-11-02P"))
    )
    (comp (ref "H12")
      (value "PZ254V-11-02P")
      (footprint "easyedapro:HDR-TH_2P-P2.54-V-M")
      (fields (field (name "Manufacturer") "XFCN(兴飞)"))
      (libsource (lib "easyedapro") (part "PZ254V-11-02P"))
    )
    (comp (ref "LED13")
      (value "TLDR5400")
      (footprint "easyedapro:LED-TH_BD5.8-P2.54-FD_RED")
      (fields (field (name "Manufacturer") "VISHAY(威世)"))
      (libsource (lib "easyedapro") (part "TLDR5400"))
    )
    (comp (ref "LED14")
      (value "TLDR5400")
      (footprint "easyedapro:LED-TH_BD5.8-P2.54-FD_RED")
      (fields (field (name "Manufacturer") "VISHAY(威世)"))
      (libsource (lib "easyedapro") (part "TLDR5400"))
    )
    (comp (ref "LED15")
      (value "TLDR5400")
      (footprint "easyedapro:LED-TH_BD5.8-P2.54-FD_RED")
      (fields (field (name "Manufacturer") "VISHAY(威世)"))
      (libsource (lib "easyedapro") (part "TLDR5400"))
    )
    (comp (ref "LED16")
      (value "TLDR5400")
      (footprint "easyedapro:LED-TH_BD5.8-P2.54-FD_RED")
      (fields (field (name "Manufacturer") "VISHAY(威世)"))
      (libsource (lib "easyedapro") (part "TLDR5400"))
    )
    (comp (ref "LED17")
      (value "TLDR5400")
      (footprint "easyedapro:LED-TH_BD5.8-P2.54-FD_RED")
      (fields (field (name "Manufacturer") "VISHAY(威世)"))
      (libsource (lib "easyedapro") (part "TLDR5400"))
    )
    (comp (ref "LED18")
      (value "TLDR5400")
      (footprint "easyedapro:LED-TH_BD5.8-P2.54-FD_RED")
      (fields (field (name "Manufacturer") "VISHAY(威世)"))
      (libsource (lib "easyedapro") (part "TLDR5400"))
    )
    (comp (ref "Q3")
      (value "SS8050(RANGE:200-350)")
      (footprint "easyedapro:SOT-23-3_L2.9-W1.3-P1.90-LS2.4-BR")
      (description "晶体管类型:NPN;集电极电流(Ic):1.5A;集射极击穿电压(Vceo):25V;耗散功率(Pd):300mW;直流电流增益(hFE):200@800mA,1V;")
      (fields (field (name "Manufacturer") "CJ(江苏长电/长晶)"))
      (libsource (lib "easyedapro") (part "SS8050_C2150"))
    )
    (comp (ref "R3")
      (value "1kΩ")
      (footprint "easyedapro:RES-TH_BD2.5-L6.5-P10.50-D0.6")
      (description "电阻类型:金属膜电阻;阻值:1kΩ;精度:±1%;功率:250mW;温度系数:±50ppm/°C;")
      (fields
        (field (name "Manufacturer Part") "MFR0W4F1001A50")
        (field (name "Manufacturer") "UNI-ROYAL(厚声)")
      )
      (libsource (lib "easyedapro") (part "MFR0W4F1001A50"))
    )
    (comp (ref "RN3")
      (value "10kΩ")
      (footprint "easyedapro:RES-ARRAY-TH_9P-P2.54-D1.0")
      (description "电阻器数:8;阻值:10kΩ;精度:±5%;单个元件功率:125mW;温度系数:±100ppm/°C;")
      (fields (field (name "Manufacturer Part") "A09-103JP") (field (name "Manufacturer") "FH(风华)"))
      (libsource (lib "easyedapro") (part "A09-103JP"))
    )
    (comp (ref "SW8")
      (value "KH-6X6X5H-STM")
      (footprint "easyedapro:SW-SMD_4P-L6.0-W6.0-P4.50-LS9.0_H5.0")
      (description "电路结构:单刀单掷;按钮形状:圆形按钮;安装方式:立贴;开关长度:6mm;开关宽度:6mm;开关高度:5mm;带支架:不带支架;触点电流:50mA;额定电压:12V;工作寿命:8万次;")
      (fields (field (name "Manufacturer") "kinghelm(金航标)"))
      (libsource (lib "easyedapro") (part "KH-6X6X5H-STM"))
    )
    (comp (ref "SW11")
      (value "KH-6X6X5H-STM")
      (footprint "easyedapro:SW-SMD_4P-L6.0-W6.0-P4.50-LS9.0_H5.0")
      (description "电路结构:单刀单掷;按钮形状:圆形按钮;安装方式:立贴;开关长度:6mm;开关宽度:6mm;开关高度:5mm;带支架:不带支架;触点电流:50mA;额定电压:12V;工作寿命:8万次;")
      (fields (field (name "Manufacturer") "kinghelm(金航标)"))
      (libsource (lib "easyedapro") (part "KH-6X6X5H-STM"))
    )
    (comp (ref "U11")
      (value "STC89C52RC-40I-PDIP40")
      (footprint "easyedapro:DIP-40_L52.0-W13.7-P2.54-LS15.2-BL")
      (description "CPU内核:51家族;CPU最大主频:-;")
      (fields (field (name "Manufacturer") "STC"))
      (libsource (lib "easyedapro") (part "STC89C52RC-40I"))
    )
    (comp (ref "U12")
      (value "10kΩ")
      (footprint "easyedapro:RES-TH_BD2.3-L6.3-P10.30-D0.6")
      (description "电阻类型:金属膜电阻;阻值:10kΩ;精度:±1%;功率:600mW;温度系数:±50ppm/°C;")
      (fields
        (field (name "Manufacturer Part") "LR1F10K")
        (field (name "Manufacturer") "TE Connectivity(泰科电子)")
      )
      (libsource (lib "easyedapro") (part "LR1F10K"))
    )
    (comp (ref "U13")
      (value "HS96L03W2C03")
      (footprint "easyedapro:OLED-TH_L27.8-W27.2-P2.54_C9900033791")
      (description "主控芯片:SSD1315;接口类型:I2C;尺寸(inch):0.96;像素分辨率:128x64;")
      (fields (field (name "Manufacturer") "HS(汉昇)"))
      (libsource (lib "easyedapro") (part "HS96L03W2C03"))
    )
    (comp (ref "U14")
      (value "DS18B20(UMW)")
      (footprint "easyedapro:TO-92-3_L4.9-W3.7-P1.27-L")
      (description "温度范围:-55°C~+125°C;精度:±0.4°C;接口类型:-;")
      (fields (field (name "Manufacturer") "UMW(友台半导体)"))
      (libsource (lib "easyedapro") (part "DS18B20"))
    )
    (comp (ref "U15")
      (value "DS1302-TD")
      (footprint "easyedapro:SOP-8_L4.9-W3.9-P1.27-LS6.0-BL")
      (description "接口类型:SPI;晶振:外置;闹钟输出:有;")
      (fields (field (name "Manufacturer") "TDSEMIC(拓电半导体)"))
      (libsource (lib "easyedapro") (part "DS1302-TD"))
    )
    (comp (ref "X5")
      (value "11.0592MHz")
      (footprint "easyedapro:HC-49US_L11.5-W4.5-P4.88")
      (description "晶振类型:直插晶振;频率:11.0592MHz;常温频差:±20ppm;负载电容:20pF;频率稳定度:±30ppm;")
      (fields
        (field (name "Manufacturer Part") "X49SD110592MSD2SC")
        (field (name "Manufacturer") "YXC(扬兴晶振)")
      )
      (libsource (lib "easyedapro") (part "X49SD110592MSD2SC"))
    )
    (comp (ref "X6")
      (value "32.768kHz")
      (footprint "easyedapro:OSC-TH_BD3.1-P0.8-D0.3")
      (description "晶振类型:直插晶振;频率:32.768kHz;常温频差:±10ppm;负载电容:12.5pF;频率稳定度:±20ppm;")
      (fields (field (name "Manufacturer Part") "X308032768KGB2SC") (field (name "Manufacturer") "YXC(扬兴晶振)"))
      (libsource (lib "easyedapro") (part "X308032768KGB2SC"))
    )
  )
  (nets
    (net (code "1") (name "+5V") (class "Default")
      (node (ref "BUZZER1") (pin "1") (pinfunction "1_1") (pintype "unspecified"))
      (node (ref "BUZZER2") (pin "1") (pinfunction "1_1") (pintype "unspecified"))
      (node (ref "BUZZER3") (pin "1") (pinfunction "1_1") (pintype "unspecified"))
      (node (ref "C14") (pin "1") (pinfunction "1_1") (pintype "input"))
      (node (ref "C3") (pin "1") (pinfunction "1_1") (pintype "input"))
      (node (ref "C9") (pin "1") (pinfunction "1_1") (pintype "input"))
      (node (ref "H10") (pin "1") (pinfunction "1_1") (pintype "unspecified"))
      (node (ref "H11") (pin "1") (pinfunction "1_1") (pintype "unspecified"))
      (node (ref "H12") (pin "1") (pinfunction "1_1") (pintype "unspecified"))
      (node (ref "RN1") (pin "1") (pinfunction "1_1") (pintype "input"))
      (node (ref "RN2") (pin "1") (pinfunction "1_1") (pintype "input"))
      (node (ref "RN3") (pin "1") (pinfunction "1_1") (pintype "input"))
      (node (ref "SW2") (pin "1") (pinfunction "1_1") (pintype "unspecified"))
      (node (ref "SW2") (pin "2") (pinfunction "2_2") (pintype "unspecified"))
      (node (ref "SW7") (pin "1") (pinfunction "1_1") (pintype "unspecified"))
      (node (ref "SW7") (pin "2") (pinfunction "2_2") (pintype "unspecified"))
      (node (ref "SW8") (pin "1") (pinfunction "1_1") (pintype "unspecified"))
      (node (ref "SW8") (pin "2") (pinfunction "2_2") (pintype "unspecified"))
      (node (ref "SW9") (pin "2") (pinfunction "2_2") (pintype "unspecified"))
      (node (ref "U1") (pin "31") (pinfunction "EA#_31") (pintype "unspecified"))
      (node (ref "U1") (pin "40") (pinfunction "VCC_40") (pintype "unspecified"))
      (node (ref "U10") (pin "1") (pinfunction "VCC2_1") (pintype "unspecified"))
      (node (ref "U11") (pin "31") (pinfunction "EA#_31") (pintype "unspecified"))
      (node (ref "U11") (pin "40") (pinfunction "VCC_40") (pintype "unspecified"))
      (node (ref "U13") (pin "2") (pinfunction "VCC_2") (pintype "unspecified"))
      (node (ref "U14") (pin "3") (pinfunction "VDD_3") (pintype "unspecified"))
      (node (ref "U15") (pin "1") (pinfunction "VCC2_1") (pintype "unspecified"))
      (node (ref "U16") (pin "5") (pinfunction "VCC_5") (pintype "unspecified"))
      (node (ref "U3") (pin "2") (pinfunction "VCC_2") (pintype "unspecified"))
      (node (ref "U4") (pin "3") (pinfunction "VDD_3") (pintype "unspecified"))
      (node (ref "U5") (pin "1") (pinfunction "VCC2_1") (pintype "unspecified"))
      (node (ref "U6") (pin "31") (pinfunction "EA#_31") (pintype "unspecified"))
      (node (ref "U6") (pin "40") (pinfunction "VCC_40") (pintype "unspecified"))
      (node (ref "U8") (pin "2") (pinfunction "VCC_2") (pintype "unspecified"))
      (node (ref "U9") (pin "3") (pinfunction "VDD_3") (pintype "unspecified"))
    )
    (net (code "2") (name "1") (class "Default")
      (node (ref "H5") (pin "2") (pinfunction "2_2") (pintype "unspecified"))
      (node (ref "U1") (pin "11") (pinfunction "TXD/P3.1_11") (pintype "unspecified"))
    )
    (net (code "3") (name "1TXD") (class "Default")
      (node (ref "H5") (pin "1") (pinfunction "1_1") (pintype "unspecified"))
      (node (ref "H6") (pin "1") (pinfunction "1_1") (pintype "unspecified"))
      (node (ref "H8") (pin "1") (pinfunction "1_1") (pintype "unspecified"))
    )
    (net (code "4") (name "2") (class "Default")
      (node (ref "H6") (pin "2") (pinfunction "2_2") (pintype "unspecified"))
      (node (ref "U6") (pin "10") (pinfunction "RXD/P3.0_10") (pintype "unspecified"))
    )
    (net (code "5") (name "3") (class "Default")
      (node (ref "H7") (pin "2") (pinfunction "2_2") (pintype "unspecified"))
      (node (ref "U6") (pin "11") (pinfunction "TXD/P3.1_11") (pintype "unspecified"))
    )
    (net (code "6") (name "4") (class "Default")
      (node (ref "H8") (pin "2") (pinfunction "2_2") (pintype "unspecified"))
      (node (ref "U11") (pin "10") (pinfunction "RXD/P3.0_10") (pintype "unspecified"))
    )
    (net (code "7") (name "5") (class "Default")
      (node (ref "H9") (pin "2") (pinfunction "2_2") (pintype "unspecified"))
      (node (ref "U11") (pin "11") (pinfunction "TXD/P3.1_11") (pintype "unspecified"))
    )
    (net (code "8") (name "A") (class "Default")
      (node (ref "H7") (pin "1") (pinfunction "1_1") (pintype "unspecified"))
      (node (ref "U16") (pin "2") (pinfunction "A_2") (pintype "unspecified"))
    )
    (net (code "9") (name "B") (class "Default")
      (node (ref "H9") (pin "1") (pinfunction "1_1") (pintype "unspecified"))
      (node (ref "U16") (pin "1") (pinfunction "B_1") (pintype "unspecified"))
    )
    (net (code "10") (name "BUZZER1") (class "Default")
      (node (ref "R1") (pin "1") (pinfunction "1_1") (pintype "input"))
      (node (ref "U1") (pin "8") (pinfunction "P1.7_8") (pintype "unspecified"))
    )
    (net (code "11") (name "BUZZER2") (class "Default")
      (node (ref "R2") (pin "1") (pinfunction "1_1") (pintype "input"))
      (node (ref "U6") (pin "8") (pinfunction "P1.7_8") (pintype "unspecified"))
    )
    (net (code "12") (name "BUZZER3") (class "Default")
      (node (ref "R3") (pin "1") (pinfunction "1_1") (pintype "input"))
      (node (ref "U11") (pin "8") (pinfunction "P1.7_8") (pintype "unspecified"))
    )
    (net (code "13") (name "C1_SW1") (class "Default")
      (node (ref "SW10") (pin "1") (pinfunction "1_1") (pintype "unspecified"))
      (node (ref "SW10") (pin "2") (pinfunction "2_2") (pintype "unspecified"))
      (node (ref "U6") (pin "12") (pinfunction "INT0#/P3.2_12") (pintype "unspecified"))
    )
    (net (code "14") (name "C2_SW1") (class "Default")
      (node (ref "SW11") (pin "1") (pinfunction "1_1") (pintype "unspecified"))
      (node (ref "SW11") (pin "2") (pinfunction "2_2") (pintype "unspecified"))
      (node (ref "U11") (pin "12") (pinfunction "INT0#/P3.2_12") (pintype "unspecified"))
    )
    (net (code "15") (name "CE1.1") (class "Default")
      (node (ref "U1") (pin "5") (pinfunction "P1.4_5") (pintype "unspecified"))
      (node (ref "U5") (pin "5") (pinfunction "CE_5") (pintype "unspecified"))
    )
    (net (code "16") (name "CE1.2") (class "Default")
      (node (ref "U10") (pin "5") (pinfunction "CE_5") (pintype "unspecified"))
      (node (ref "U6") (pin "5") (pinfunction "P1.4_5") (pintype "unspecified"))
    )
    (net (code "17") (name "CE1.3") (class "Default")
      (node (ref "U11") (pin "5") (pinfunction "P1.4_5") (pintype "unspecified"))
      (node (ref "U15") (pin "5") (pinfunction "CE_5") (pintype "unspecified"))
    )
    (net (code "18") (name "DQ1") (class "Default")
      (node (ref "U1") (pin "6") (pinfunction "P1.5_6") (pintype "unspecified"))
      (node (ref "U4") (pin "2") (pinfunction "DQ_2") (pintype "unspecified"))
    )
    (net (code "19") (name "DQ2") (class "Default")
      (node (ref "U6") (pin "6") (pinfunction "P1.5_6") (pintype "unspecified"))
      (node (ref "U9") (pin "2") (pinfunction "DQ_2") (pintype "unspecified"))
    )
    (net (code "20") (name "DQ3") (class "Default")
      (node (ref "U11") (pin "6") (pinfunction "P1.5_6") (pintype "unspecified"))
      (node (ref "U14") (pin "2") (pinfunction "DQ_2") (pintype "unspecified"))
    )
    (net (code "21") (name "GND") (class "Default")
      (node (ref "C10") (pin "1") (pinfunction "1_1") (pintype "input"))
      (node (ref "C11") (pin "1") (pinfunction "1_1") (pintype "input"))
      (node (ref "C12") (pin "1") (pinfunction "1_1") (pintype "input"))
      (node (ref "C13") (pin "1") (pinfunction "1_1") (pintype "input"))
      (node (ref "C15") (pin "1") (pinfunction "1_1") (pintype "input"))
      (node (ref "C16") (pin "1") (pinfunction "1_1") (pintype "input"))
      (node (ref "C2") (pin "1") (pinfunction "1_1") (pintype "input"))
      (node (ref "C4") (pin "1") (pinfunction "1_1") (pintype "input"))
      (node (ref "C5") (pin "1") (pinfunction "1_1") (pintype "input"))
      (node (ref "C6") (pin "1") (pinfunction "1_1") (pintype "input"))
      (node (ref "C7") (pin "1") (pinfunction "1_1") (pintype "input"))
      (node (ref "C8") (pin "1") (pinfunction "1_1") (pintype "input"))
      (node (ref "H1") (pin "2") (pinfunction "2_2") (pintype "unspecified"))
      (node (ref "H10") (pin "2") (pinfunction "2_2") (pintype "unspecified"))
      (node (ref "H11") (pin "2") (pinfunction "2_2") (pintype "unspecified"))
      (node (ref "H12") (pin "2") (pinfunction "2_2") (pintype "unspecified"))
      (node (ref "LED1") (pin "2") (pinfunction "K_2") (pintype "unspecified"))
      (node (ref "LED10") (pin "2") (pinfunction "K_2") (pintype "unspecified"))
      (node (ref "LED11") (pin "2") (pinfunction "K_2") (pintype "unspecified"))
      (node (ref "LED12") (pin "2") (pinfunction "K_2") (pintype "unspecified"))
      (node (ref "LED13") (pin "2") (pinfunction "K_2") (pintype "unspecified"))
      (node (ref "LED14") (pin "2") (pinfunction "K_2") (pintype "unspecified"))
      (node (ref "LED15") (pin "2") (pinfunction "K_2") (pintype "unspecified"))
      (node (ref "LED16") (pin "2") (pinfunction "K_2") (pintype "unspecified"))
      (node (ref "LED17") (pin "2") (pinfunction "K_2") (pintype "unspecified"))
      (node (ref "LED18") (pin "2") (pinfunction "K_2") (pintype "unspecified"))
      (node (ref "LED2") (pin "2") (pinfunction "K_2") (pintype "unspecified"))
      (node (ref "LED3") (pin "2") (pinfunction "K_2") (pintype "unspecified"))
      (node (ref "LED4") (pin "2") (pinfunction "K_2") (pintype "unspecified"))
      (node (ref "LED5") (pin "2") (pinfunction "K_2") (pintype "unspecified"))
      (node (ref "LED6") (pin "2") (pinfunction "K_2") (pintype "unspecified"))
      (node (ref "LED7") (pin "2") (pinfunction "K_2") (pintype "unspecified"))
      (node (ref "LED8") (pin "2") (pinfunction "K_2") (pintype "unspecified"))
      (node (ref "LED9") (pin "2") (pinfunction "K_2") (pintype "unspecified"))
      (node (ref "Q1") (pin "2") (pinfunction "E_2") (pintype "unspecified"))
      (node (ref "Q2") (pin "2") (pinfunction "E_2") (pintype "unspecified"))
      (node (ref "Q3") (pin "2") (pinfunction "E_2") (pintype "unspecified"))
      (node (ref "R4") (pin "2") (pinfunction "2_2") (pintype "unspecified"))
      (node (ref "R5") (pin "2") (pinfunction "2_2") (pintype "unspecified"))
      (node (ref "SW10") (pin "3") (pinfunction "3_3") (pintype "unspecified"))
      (node (ref "SW10") (pin "4") (pinfunction "4_4") (pintype "unspecified"))
      (node (ref "SW11") (pin "3") (pinfunction "3_3") (pintype "unspecified"))
      (node (ref "SW11") (pin "4") (pinfunction "4_4") (pintype "unspecified"))
      (node (ref "SW3") (pin "3") (pinfunction "3_3") (pintype "unspecified"))
      (node (ref "SW3") (pin "4") (pinfunction "4_4") (pintype "unspecified"))
      (node (ref "SW4") (pin "3") (pinfunction "3_3") (pintype "unspecified"))
      (node (ref "SW4") (pin "4") (pinfunction "4_4") (pintype "unspecified"))
      (node (ref "SW5") (pin "3") (pinfunction "3_3") (pintype "unspecified"))
      (node (ref "SW5") (pin "4") (pinfunction "4_4") (pintype "unspecified"))
      (node (ref "SW6") (pin "3") (pinfunction "3_3") (pintype "unspecified"))
      (node (ref "SW6") (pin "4") (pinfunction "4_4") (pintype "unspecified"))
      (node (ref "U1") (pin "20") (pinfunction "GND_20") (pintype "unspecified"))
      (node (ref "U10") (pin "4") (pinfunction "GND_4") (pintype "unspecified"))
      (node (ref "U11") (pin "20") (pinfunction "GND_20") (pintype "unspecified"))
      (node (ref "U12") (pin "1") (pinfunction "1_1") (pintype "unspecified"))
      (node (ref "U13") (pin "1") (pinfunction "GND_1") (pintype "unspecified"))
      (node (ref "U14") (pin "1") (pinfunction "GND_1") (pintype "unspecified"))
      (node (ref "U15") (pin "4") (pinfunction "GND_4") (pintype "unspecified"))
      (node (ref "U16") (pin "3") (pinfunction "GND_3") (pintype "unspecified"))
      (node (ref "U2") (pin "1") (pinfunction "1_1") (pintype "unspecified"))
      (node (ref "U3") (pin "1") (pinfunction "GND_1") (pintype "unspecified"))
      (node (ref "U4") (pin "1") (pinfunction "GND_1") (pintype "unspecified"))
      (node (ref "U5") (pin "4") (pinfunction "GND_4") (pintype "unspecified"))
      (node (ref "U6") (pin "20") (pinfunction "GND_20") (pintype "unspecified"))
      (node (ref "U7") (pin "1") (pinfunction "1_1") (pintype "unspecified"))
      (node (ref "U8") (pin "1") (pinfunction "GND_1") (pintype "unspecified"))
      (node (ref "U9") (pin "1") (pinfunction "GND_1") (pintype "unspecified"))
      (node (ref "USB1") (pin "A12") (pinfunction "GND_A12") (pintype "unspecified"))
      (node (ref "USB1") (pin "B12") (pinfunction "GND_B12") (pintype "unspecified"))
    )
    (net (code "22") (name "IO1.1") (class "Default")
      (node (ref "U1") (pin "4") (pinfunction "P1.3_4") (pintype "unspecified"))
      (node (ref "U5") (pin "6") (pinfunction "I/O_6") (pintype "unspecified"))
    )
    (net (code "23") (name "IO1.2") (class "Default")
      (node (ref "U10") (pin "6") (pinfunction "I/O_6") (pintype "unspecified"))
      (node (ref "U6") (pin "4") (pinfunction "P1.3_4") (pintype "unspecified"))
    )
    (net (code "24") (name "IO1.3") (class "Default")
      (node (ref "U11") (pin "4") (pinfunction "P1.3_4") (pintype "unspecified"))
      (node (ref "U15") (pin "6") (pinfunction "I/O_6") (pintype "unspecified"))
    )
    (net (code "25") (name "Net-(LED1-A)") (class "Default")
      (node (ref "LED1") (pin "1") (pinfunction "A_1") (pintype "unspecified"))
      (node (ref "U1") (pin "28") (pinfunction "P2.7_28") (pintype "unspecified"))
    )
    (net (code "26") (name "Net-(LED2-A)") (class "Default")
      (node (ref "LED2") (pin "1") (pinfunction "A_1") (pintype "unspecified"))
      (node (ref "U1") (pin "27") (pinfunction "P2.6_27") (pintype "unspecified"))
    )
    (net (code "27") (name "Net-(LED3-A)") (class "Default")
      (node (ref "LED3") (pin "1") (pinfunction "A_1") (pintype "unspecified"))
      (node (ref "U1") (pin "26") (pinfunction "P2.5_26") (pintype "unspecified"))
    )
    (net (code "28") (name "Net-(LED4-A)") (class "Default")
      (node (ref "LED4") (pin "1") (pinfunction "A_1") (pintype "unspecified"))
      (node (ref "U1") (pin "25") (pinfunction "P2.4_25") (pintype "unspecified"))
    )
    (net (code "29") (name "Net-(LED5-A)") (class "Default")
      (node (ref "LED5") (pin "1") (pinfunction "A_1") (pintype "unspecified"))
      (node (ref "U1") (pin "24") (pinfunction "P2.3_24") (pintype "unspecified"))
    )
    (net (code "30") (name "Net-(LED6-A)") (class "Default")
      (node (ref "LED6") (pin "1") (pinfunction "A_1") (pintype "unspecified"))
      (node (ref "U1") (pin "23") (pinfunction "P2.2_23") (pintype "unspecified"))
    )
    (net (code "31") (name "Net-(LED7-A)") (class "Default")
      (node (ref "LED7") (pin "1") (pinfunction "A_1") (pintype "unspecified"))
      (node (ref "U6") (pin "28") (pinfunction "P2.7_28") (pintype "unspecified"))
    )
    (net (code "32") (name "Net-(LED8-A)") (class "Default")
      (node (ref "LED8") (pin "1") (pinfunction "A_1") (pintype "unspecified"))
      (node (ref "U6") (pin "27") (pinfunction "P2.6_27") (pintype "unspecified"))
    )
    (net (code "33") (name "Net-(LED9-A)") (class "Default")
      (node (ref "LED9") (pin "1") (pinfunction "A_1") (pintype "unspecified"))
      (node (ref "U6") (pin "26") (pinfunction "P2.5_26") (pintype "unspecified"))
    )
    (net (code "34") (name "Net-(LED10-A)") (class "Default")
      (node (ref "LED10") (pin "1") (pinfunction "A_1") (pintype "unspecified"))
      (node (ref "U6") (pin "25") (pinfunction "P2.4_25") (pintype "unspecified"))
    )
    (net (code "35") (name "Net-(LED11-A)") (class "Default")
      (node (ref "LED11") (pin "1") (pinfunction "A_1") (pintype "unspecified"))
      (node (ref "U6") (pin "24") (pinfunction "P2.3_24") (pintype "unspecified"))
    )
    (net (code "36") (name "Net-(LED12-A)") (class "Default")
      (node (ref "LED12") (pin "1") (pinfunction "A_1") (pintype "unspecified"))
      (node (ref "U6") (pin "23") (pinfunction "P2.2_23") (pintype "unspecified"))
    )
    (net (code "37") (name "Net-(LED13-A)") (class "Default")
      (node (ref "LED13") (pin "1") (pinfunction "A_1") (pintype "unspecified"))
      (node (ref "U11") (pin "28") (pinfunction "P2.7_28") (pintype "unspecified"))
    )
    (net (code "38") (name "Net-(LED14-A)") (class "Default")
      (node (ref "LED14") (pin "1") (pinfunction "A_1") (pintype "unspecified"))
      (node (ref "U11") (pin "27") (pinfunction "P2.6_27") (pintype "unspecified"))
    )
    (net (code "39") (name "Net-(LED15-A)") (class "Default")
      (node (ref "LED15") (pin "1") (pinfunction "A_1") (pintype "unspecified"))
      (node (ref "U11") (pin "26") (pinfunction "P2.5_26") (pintype "unspecified"))
    )
    (net (code "40") (name "Net-(LED16-A)") (class "Default")
      (node (ref "LED16") (pin "1") (pinfunction "A_1") (pintype "unspecified"))
      (node (ref "U11") (pin "25") (pinfunction "P2.4_25") (pintype "unspecified"))
    )
    (net (code "41") (name "Net-(LED17-A)") (class "Default")
      (node (ref "LED17") (pin "1") (pinfunction "A_1") (pintype "unspecified"))
      (node (ref "U11") (pin "24") (pinfunction "P2.3_24") (pintype "unspecified"))
    )
    (net (code "42") (name "Net-(LED18-A)") (class "Default")
      (node (ref "LED18") (pin "1") (pinfunction "A_1") (pintype "unspecified"))
      (node (ref "U11") (pin "23") (pinfunction "P2.2_23") (pintype "unspecified"))
    )
    (net (code "43") (name "Net-(Q1-B)") (class "Default")
      (node (ref "Q1") (pin "1") (pinfunction "B_1") (pintype "unspecified"))
      (node (ref "R1") (pin "2") (pinfunction "2_2") (pintype "input"))
    )
    (net (code "44") (name "Net-(Q1-C)") (class "Default")
      (node (ref "BUZZER1") (pin "2") (pinfunction "2_2") (pintype "unspecified"))
      (node (ref "Q1") (pin "3") (pinfunction "C_3") (pintype "unspecified"))
    )
    (net (code "45") (name "Net-(Q2-B)") (class "Default")
      (node (ref "Q2") (pin "1") (pinfunction "B_1") (pintype "unspecified"))
      (node (ref "R2") (pin "2") (pinfunction "2_2") (pintype "input"))
    )
    (net (code "46") (name "Net-(Q2-C)") (class "Default")
      (node (ref "BUZZER2") (pin "2") (pinfunction "2_2") (pintype "unspecified"))
      (node (ref "Q2") (pin "3") (pinfunction "C_3") (pintype "unspecified"))
    )
    (net (code "47") (name "Net-(Q3-B)") (class "Default")
      (node (ref "Q3") (pin "1") (pinfunction "B_1") (pintype "unspecified"))
      (node (ref "R3") (pin "2") (pinfunction "2_2") (pintype "input"))
    )
    (net (code "48") (name "Net-(Q3-C)") (class "Default")
      (node (ref "BUZZER3") (pin "2") (pinfunction "2_2") (pintype "unspecified"))
      (node (ref "Q3") (pin "3") (pinfunction "C_3") (pintype "unspecified"))
    )
    (net (code "49") (name "Net-(U1-P0.0)") (class "Default")
      (node (ref "RN1") (pin "2") (pinfunction "2_2") (pintype "input"))
      (node (ref "U1") (pin "39") (pinfunction "P0.0_39") (pintype "unspecified"))
    )
    (net (code "50") (name "Net-(U1-P0.1)") (class "Default")
      (node (ref "RN1") (pin "3") (pinfunction "3_3") (pintype "input"))
      (node (ref "U1") (pin "38") (pinfunction "P0.1_38") (pintype "unspecified"))
    )
    (net (code "51") (name "Net-(U1-P0.2)") (class "Default")
      (node (ref "RN1") (pin "4") (pinfunction "4_4") (pintype "input"))
      (node (ref "U1") (pin "37") (pinfunction "P0.2_37") (pintype "unspecified"))
    )
    (net (code "52") (name "Net-(U1-P0.3)") (class "Default")
      (node (ref "RN1") (pin "5") (pinfunction "5_5") (pintype "input"))
      (node (ref "U1") (pin "36") (pinfunction "P0.3_36") (pintype "unspecified"))
    )
    (net (code "53") (name "Net-(U1-P0.4)") (class "Default")
      (node (ref "RN1") (pin "6") (pinfunction "6_6") (pintype "input"))
      (node (ref "U1") (pin "35") (pinfunction "P0.4_35") (pintype "unspecified"))
    )
    (net (code "54") (name "Net-(U1-P0.5)") (class "Default")
      (node (ref "RN1") (pin "7") (pinfunction "7_7") (pintype "input"))
      (node (ref "U1") (pin "34") (pinfunction "P0.5_34") (pintype "unspecified"))
    )
    (net (code "55") (name "Net-(U1-P0.6)") (class "Default")
      (node (ref "RN1") (pin "8") (pinfunction "8_8") (pintype "input"))
      (node (ref "U1") (pin "33") (pinfunction "P0.6_33") (pintype "unspecified"))
    )
    (net (code "56") (name "Net-(U1-P0.7)") (class "Default")
      (node (ref "RN1") (pin "9") (pinfunction "9_9") (pintype "input"))
      (node (ref "U1") (pin "32") (pinfunction "P0.7_32") (pintype "unspecified"))
    )
    (net (code "57") (name "Net-(U1-RST)") (class "Default")
      (node (ref "C3") (pin "2") (pinfunction "2_2") (pintype "input"))
      (node (ref "SW2") (pin "3") (pinfunction "3_3") (pintype "unspecified"))
      (node (ref "SW2") (pin "4") (pinfunction "4_4") (pintype "unspecified"))
      (node (ref "U1") (pin "9") (pinfunction "RST_9") (pintype "unspecified"))
      (node (ref "U2") (pin "2") (pinfunction "2_2") (pintype "unspecified"))
    )
    (net (code "58") (name "Net-(U1-RXD{slash}P3.0)") (class "Default")
      (node (ref "H4") (pin "2") (pinfunction "2_2") (pintype "unspecified"))
      (node (ref "U1") (pin "10") (pinfunction "RXD/P3.0_10") (pintype "unspecified"))
    )
    (net (code "59") (name "Net-(U1-XTAL1)") (class "Default")
      (node (ref "C2") (pin "2") (pinfunction "2_2") (pintype "input"))
      (node (ref "U1") (pin "19") (pinfunction "XTAL1_19") (pintype "unspecified"))
      (node (ref "X1") (pin "2") (pinfunction "OSC2_2") (pintype "input"))
    )
    (net (code "60") (name "Net-(U1-XTAL2)") (class "Default")
      (node (ref "C4") (pin "2") (pinfunction "2_2") (pintype "input"))
      (node (ref "U1") (pin "18") (pinfunction "XTAL2_18") (pintype "unspecified"))
      (node (ref "X1") (pin "1") (pinfunction "OSC1_1") (pintype "input"))
    )
    (net (code "61") (name "Net-(U5-X1)") (class "Default")
      (node (ref "C5") (pin "2") (pinfunction "2_2") (pintype "input"))
      (node (ref "U5") (pin "2") (pinfunction "X1_2") (pintype "unspecified"))
      (node (ref "X2") (pin "2") (pinfunction "OSC2_2") (pintype "unspecified"))
    )
    (net (code "62") (name "Net-(U5-X2)") (class "Default")
      (node (ref "C6") (pin "2") (pinfunction "2_2") (pintype "input"))
      (node (ref "U5") (pin "3") (pinfunction "X2_3") (pintype "unspecified"))
      (node (ref "X2") (pin "1") (pinfunction "OSC1_1") (pintype "unspecified"))
    )
    (net (code "63") (name "Net-(U6-P0.0)") (class "Default")
      (node (ref "RN2") (pin "2") (pinfunction "2_2") (pintype "input"))
      (node (ref "U6") (pin "39") (pinfunction "P0.0_39") (pintype "unspecified"))
    )
    (net (code "64") (name "Net-(U6-P0.1)") (class "Default")
      (node (ref "RN2") (pin "3") (pinfunction "3_3") (pintype "input"))
      (node (ref "U6") (pin "38") (pinfunction "P0.1_38") (pintype "unspecified"))
    )
    (net (code "65") (name "Net-(U6-P0.2)") (class "Default")
      (node (ref "RN2") (pin "4") (pinfunction "4_4") (pintype "input"))
      (node (ref "U6") (pin "37") (pinfunction "P0.2_37") (pintype "unspecified"))
    )
    (net (code "66") (name "Net-(U6-P0.3)") (class "Default")
      (node (ref "RN2") (pin "5") (pinfunction "5_5") (pintype "input"))
      (node (ref "U6") (pin "36") (pinfunction "P0.3_36") (pintype "unspecified"))
    )
    (net (code "67") (name "Net-(U6-P0.4)") (class "Default")
      (node (ref "RN2") (pin "6") (pinfunction "6_6") (pintype "input"))
      (node (ref "U6") (pin "35") (pinfunction "P0.4_35") (pintype "unspecified"))
    )
    (net (code "68") (name "Net-(U6-P0.5)") (class "Default")
      (node (ref "RN2") (pin "7") (pinfunction "7_7") (pintype "input"))
      (node (ref "U6") (pin "34") (pinfunction "P0.5_34") (pintype "unspecified"))
    )
    (net (code "69") (name "Net-(U6-P0.6)") (class "Default")
      (node (ref "RN2") (pin "8") (pinfunction "8_8") (pintype "input"))
      (node (ref "U6") (pin "33") (pinfunction "P0.6_33") (pintype "unspecified"))
    )
    (net (code "70") (name "Net-(U6-P0.7)") (class "Default")
      (node (ref "RN2") (pin "9") (pinfunction "9_9") (pintype "input"))
      (node (ref "U6") (pin "32") (pinfunction "P0.7_32") (pintype "unspecified"))
    )
    (net (code "71") (name "Net-(U6-RST)") (class "Default")
      (node (ref "C9") (pin "2") (pinfunction "2_2") (pintype "input"))
      (node (ref "SW7") (pin "3") (pinfunction "3_3") (pintype "unspecified"))
      (node (ref "SW7") (pin "4") (pinfunction "4_4") (pintype "unspecified"))
      (node (ref "U6") (pin "9") (pinfunction "RST_9") (pintype "unspecified"))
      (node (ref "U7") (pin "2") (pinfunction "2_2") (pintype "unspecified"))
    )
    (net (code "72") (name "Net-(U6-XTAL1)") (class "Default")
      (node (ref "C8") (pin "2") (pinfunction "2_2") (pintype "input"))
      (node (ref "U6") (pin "19") (pinfunction "XTAL1_19") (pintype "unspecified"))
      (node (ref "X3") (pin "2") (pinfunction "OSC2_2") (pintype "input"))
    )
    (net (code "73") (name "Net-(U6-XTAL2)") (class "Default")
      (node (ref "C7") (pin "2") (pinfunction "2_2") (pintype "input"))
      (node (ref "U6") (pin "18") (pinfunction "XTAL2_18") (pintype "unspecified"))
      (node (ref "X3") (pin "1") (pinfunction "OSC1_1") (pintype "input"))
    )
    (net (code "74") (name "Net-(U10-X1)") (class "Default")
      (node (ref "C10") (pin "2") (pinfunction "2_2") (pintype "input"))
      (node (ref "U10") (pin "2") (pinfunction "X1_2") (pintype "unspecified"))
      (node (ref "X4") (pin "2") (pinfunction "OSC2_2") (pintype "unspecified"))
    )
    (net (code "75") (name "Net-(U10-X2)") (class "Default")
      (node (ref "C11") (pin "2") (pinfunction "2_2") (pintype "input"))
      (node (ref "U10") (pin "3") (pinfunction "X2_3") (pintype "unspecified"))
      (node (ref "X4") (pin "1") (pinfunction "OSC1_1") (pintype "unspecified"))
    )
    (net (code "76") (name "Net-(U11-P0.0)") (class "Default")
      (node (ref "RN3") (pin "2") (pinfunction "2_2") (pintype "input"))
      (node (ref "U11") (pin "39") (pinfunction "P0.0_39") (pintype "unspecified"))
    )
    (net (code "77") (name "Net-(U11-P0.1)") (class "Default")
      (node (ref "RN3") (pin "3") (pinfunction "3_3") (pintype "input"))
      (node (ref "U11") (pin "38") (pinfunction "P0.1_38") (pintype "unspecified"))
    )
    (net (code "78") (name "Net-(U11-P0.2)") (class "Default")
      (node (ref "RN3") (pin "4") (pinfunction "4_4") (pintype "input"))
      (node (ref "U11") (pin "37") (pinfunction "P0.2_37") (pintype "unspecified"))
    )
    (net (code "79") (name "Net-(U11-P0.3)") (class "Default")
      (node (ref "RN3") (pin "5") (pinfunction "5_5") (pintype "input"))
      (node (ref "U11") (pin "36") (pinfunction "P0.3_36") (pintype "unspecified"))
    )
    (net (code "80") (name "Net-(U11-P0.4)") (class "Default")
      (node (ref "RN3") (pin "6") (pinfunction "6_6") (pintype "input"))
      (node (ref "U11") (pin "35") (pinfunction "P0.4_35") (pintype "unspecified"))
    )
    (net (code "81") (name "Net-(U11-P0.5)") (class "Default")
      (node (ref "RN3") (pin "7") (pinfunction "7_7") (pintype "input"))
      (node (ref "U11") (pin "34") (pinfunction "P0.5_34") (pintype "unspecified"))
    )
    (net (code "82") (name "Net-(U11-P0.6)") (class "Default")
      (node (ref "RN3") (pin "8") (pinfunction "8_8") (pintype "input"))
      (node (ref "U11") (pin "33") (pinfunction "P0.6_33") (pintype "unspecified"))
    )
    (net (code "83") (name "Net-(U11-P0.7)") (class "Default")
      (node (ref "RN3") (pin "9") (pinfunction "9_9") (pintype "input"))
      (node (ref "U11") (pin "32") (pinfunction "P0.7_32") (pintype "unspecified"))
    )
    (net (code "84") (name "Net-(U11-RST)") (class "Default")
      (node (ref "C14") (pin "2") (pinfunction "2_2") (pintype "input"))
      (node (ref "SW8") (pin "3") (pinfunction "3_3") (pintype "unspecified"))
      (node (ref "SW8") (pin "4") (pinfunction "4_4") (pintype "unspecified"))
      (node (ref "U11") (pin "9") (pinfunction "RST_9") (pintype "unspecified"))
      (node (ref "U12") (pin "2") (pinfunction "2_2") (pintype "unspecified"))
    )
    (net (code "85") (name "Net-(U11-XTAL1)") (class "Default")
      (node (ref "C13") (pin "2") (pinfunction "2_2") (pintype "input"))
      (node (ref "U11") (pin "19") (pinfunction "XTAL1_19") (pintype "unspecified"))
      (node (ref "X5") (pin "2") (pinfunction "OSC2_2") (pintype "input"))
    )
    (net (code "86") (name "Net-(U11-XTAL2)") (class "Default")
      (node (ref "C12") (pin "2") (pinfunction "2_2") (pintype "input"))
      (node (ref "U11") (pin "18") (pinfunction "XTAL2_18") (pintype "unspecified"))
      (node (ref "X5") (pin "1") (pinfunction "OSC1_1") (pintype "input"))
    )
    (net (code "87") (name "Net-(U15-X1)") (class "Default")
      (node (ref "C15") (pin "2") (pinfunction "2_2") (pintype "input"))
      (node (ref "U15") (pin "2") (pinfunction "X1_2") (pintype "unspecified"))
      (node (ref "X6") (pin "2") (pinfunction "OSC2_2") (pintype "unspecified"))
    )
    (net (code "88") (name "Net-(U15-X2)") (class "Default")
      (node (ref "C16") (pin "2") (pinfunction "2_2") (pintype "input"))
      (node (ref "U15") (pin "3") (pinfunction "X2_3") (pintype "unspecified"))
      (node (ref "X6") (pin "1") (pinfunction "OSC1_1") (pintype "unspecified"))
    )
    (net (code "89") (name "Net-(USB1-CC1)") (class "Default")
      (node (ref "R4") (pin "1") (pinfunction "1_1") (pintype "unspecified"))
      (node (ref "USB1") (pin "A5") (pinfunction "CC1_A5") (pintype "unspecified"))
    )
    (net (code "90") (name "Net-(USB1-CC2)") (class "Default")
      (node (ref "R5") (pin "1") (pinfunction "1_1") (pintype "unspecified"))
      (node (ref "USB1") (pin "B5") (pinfunction "CC2_B5") (pintype "unspecified"))
    )
    (net (code "91") (name "SCL1") (class "Default")
      (node (ref "U1") (pin "21") (pinfunction "P2.0_21") (pintype "unspecified"))
      (node (ref "U3") (pin "3") (pinfunction "SCL_3") (pintype "unspecified"))
    )
    (net (code "92") (name "SCL2") (class "Default")
      (node (ref "U6") (pin "21") (pinfunction "P2.0_21") (pintype "unspecified"))
      (node (ref "U8") (pin "3") (pinfunction "SCL_3") (pintype "unspecified"))
    )
    (net (code "93") (name "SCL3") (class "Default")
      (node (ref "U11") (pin "21") (pinfunction "P2.0_21") (pintype "unspecified"))
      (node (ref "U13") (pin "3") (pinfunction "SCL_3") (pintype "unspecified"))
    )
    (net (code "94") (name "SCLK1.1") (class "Default")
      (node (ref "U1") (pin "3") (pinfunction "P1.2_3") (pintype "unspecified"))
      (node (ref "U5") (pin "7") (pinfunction "SCLK_7") (pintype "unspecified"))
    )
    (net (code "95") (name "SCLK1.2") (class "Default")
      (node (ref "U10") (pin "7") (pinfunction "SCLK_7") (pintype "unspecified"))
      (node (ref "U6") (pin "3") (pinfunction "P1.2_3") (pintype "unspecified"))
    )
    (net (code "96") (name "SCLK1.3") (class "Default")
      (node (ref "U11") (pin "3") (pinfunction "P1.2_3") (pintype "unspecified"))
      (node (ref "U15") (pin "7") (pinfunction "SCLK_7") (pintype "unspecified"))
    )
    (net (code "97") (name "SDA1") (class "Default")
      (node (ref "U1") (pin "22") (pinfunction "P2.1_22") (pintype "unspecified"))
      (node (ref "U3") (pin "4") (pinfunction "SDA_4") (pintype "unspecified"))
    )
    (net (code "98") (name "SDA2") (class "Default")
      (node (ref "U6") (pin "22") (pinfunction "P2.1_22") (pintype "unspecified"))
      (node (ref "U8") (pin "4") (pinfunction "SDA_4") (pintype "unspecified"))
    )
    (net (code "99") (name "SDA3") (class "Default")
      (node (ref "U11") (pin "22") (pinfunction "P2.1_22") (pintype "unspecified"))
      (node (ref "U13") (pin "4") (pinfunction "SDA_4") (pintype "unspecified"))
    )
    (net (code "100") (name "SW1") (class "Default")
      (node (ref "SW3") (pin "1") (pinfunction "1_1") (pintype "unspecified"))
      (node (ref "SW3") (pin "2") (pinfunction "2_2") (pintype "unspecified"))
      (node (ref "U1") (pin "7") (pinfunction "P1.6_7") (pintype "unspecified"))
    )
    (net (code "101") (name "SW2") (class "Default")
      (node (ref "SW4") (pin "1") (pinfunction "1_1") (pintype "unspecified"))
      (node (ref "SW4") (pin "2") (pinfunction "2_2") (pintype "unspecified"))
      (node (ref "U1") (pin "12") (pinfunction "INT0#/P3.2_12") (pintype "unspecified"))
    )
    (net (code "102") (name "SW3") (class "Default")
      (node (ref "SW5") (pin "1") (pinfunction "1_1") (pintype "unspecified"))
      (node (ref "SW5") (pin "2") (pinfunction "2_2") (pintype "unspecified"))
      (node (ref "U1") (pin "13") (pinfunction "INT1#/P3.3_13") (pintype "unspecified"))
    )
    (net (code "103") (name "SW4") (class "Default")
      (node (ref "SW6") (pin "1") (pinfunction "1_1") (pintype "unspecified"))
      (node (ref "SW6") (pin "2") (pinfunction "2_2") (pintype "unspecified"))
      (node (ref "U1") (pin "14") (pinfunction "T0/P3.4_14") (pintype "unspecified"))
    )
    (net (code "104") (name "V0") (class "Default")
      (node (ref "H1") (pin "1") (pinfunction "1_1") (pintype "unspecified"))
      (node (ref "SW9") (pin "3") (pinfunction "3_3") (pintype "unspecified"))
      (node (ref "USB1") (pin "A9") (pinfunction "VBUS_A9") (pintype "unspecified"))
      (node (ref "USB1") (pin "B9") (pinfunction "VBUS_B9") (pintype "unspecified"))
    )
    (net (code "105") (name "Y") (class "Default")
      (node (ref "H4") (pin "1") (pinfunction "1_1") (pintype "unspecified"))
      (node (ref "U16") (pin "4") (pinfunction "Y_4") (pintype "unspecified"))
    )
    (net (code "106") (name "unconnected-(SW9-Pad1)") (class "Default")
      (node (ref "SW9") (pin "1") (pinfunction "1_1") (pintype "unspecified+no_connect"))
    )
    (net (code "107") (name "unconnected-(U1-ALE-Pad30)") (class "Default")
      (node (ref "U1") (pin "30") (pinfunction "ALE_30") (pintype "unspecified+no_connect"))
    )
    (net (code "108") (name "unconnected-(U1-PSEN#-Pad29)") (class "Default")
      (node (ref "U1") (pin "29") (pinfunction "PSEN#_29") (pintype "unspecified+no_connect"))
    )
    (net (code "109") (name "unconnected-(U1-RD#{slash}P3.7-Pad17)") (class "Default")
      (node (ref "U1") (pin "17") (pinfunction "RD#/P3.7_17") (pintype "unspecified+no_connect"))
    )
    (net (code "110") (name "unconnected-(U1-T1{slash}P3.5-Pad15)") (class "Default")
      (node (ref "U1") (pin "15") (pinfunction "T1/P3.5_15") (pintype "unspecified+no_connect"))
    )
    (net (code "111") (name "unconnected-(U1-T2EX{slash}P1.1-Pad2)") (class "Default")
      (node (ref "U1") (pin "2") (pinfunction "T2EX/P1.1_2") (pintype "unspecified+no_connect"))
    )
    (net (code "112") (name "unconnected-(U1-T2{slash}P1.0-Pad1)") (class "Default")
      (node (ref "U1") (pin "1") (pinfunction "T2/P1.0_1") (pintype "unspecified+no_connect"))
    )
    (net (code "113") (name "unconnected-(U1-WR#{slash}P3.6-Pad16)") (class "Default")
      (node (ref "U1") (pin "16") (pinfunction "WR#/P3.6_16") (pintype "unspecified+no_connect"))
    )
    (net (code "114") (name "unconnected-(U5-VCC1-Pad8)") (class "Default")
      (node (ref "U5") (pin "8") (pinfunction "VCC1_8") (pintype "unspecified+no_connect"))
    )
    (net (code "115") (name "unconnected-(U6-ALE-Pad30)") (class "Default")
      (node (ref "U6") (pin "30") (pinfunction "ALE_30") (pintype "unspecified+no_connect"))
    )
    (net (code "116") (name "unconnected-(U6-INT1#{slash}P3.3-Pad13)") (class "Default")
      (node (ref "U6") (pin "13") (pinfunction "INT1#/P3.3_13") (pintype "unspecified+no_connect"))
    )
    (net (code "117") (name "unconnected-(U6-P1.6-Pad7)") (class "Default")
      (node (ref "U6") (pin "7") (pinfunction "P1.6_7") (pintype "unspecified+no_connect"))
    )
    (net (code "118") (name "unconnected-(U6-PSEN#-Pad29)") (class "Default")
      (node (ref "U6") (pin "29") (pinfunction "PSEN#_29") (pintype "unspecified+no_connect"))
    )
    (net (code "119") (name "unconnected-(U6-RD#{slash}P3.7-Pad17)") (class "Default")
      (node (ref "U6") (pin "17") (pinfunction "RD#/P3.7_17") (pintype "unspecified+no_connect"))
    )
    (net (code "120") (name "unconnected-(U6-T0{slash}P3.4-Pad14)") (class "Default")
      (node (ref "U6") (pin "14") (pinfunction "T0/P3.4_14") (pintype "unspecified+no_connect"))
    )
    (net (code "121") (name "unconnected-(U6-T1{slash}P3.5-Pad15)") (class "Default")
      (node (ref "U6") (pin "15") (pinfunction "T1/P3.5_15") (pintype "unspecified+no_connect"))
    )
    (net (code "122") (name "unconnected-(U6-T2EX{slash}P1.1-Pad2)") (class "Default")
      (node (ref "U6") (pin "2") (pinfunction "T2EX/P1.1_2") (pintype "unspecified+no_connect"))
    )
    (net (code "123") (name "unconnected-(U6-T2{slash}P1.0-Pad1)") (class "Default")
      (node (ref "U6") (pin "1") (pinfunction "T2/P1.0_1") (pintype "unspecified+no_connect"))
    )
    (net (code "124") (name "unconnected-(U6-WR#{slash}P3.6-Pad16)") (class "Default")
      (node (ref "U6") (pin "16") (pinfunction "WR#/P3.6_16") (pintype "unspecified+no_connect"))
    )
    (net (code "125") (name "unconnected-(U10-VCC1-Pad8)") (class "Default")
      (node (ref "U10") (pin "8") (pinfunction "VCC1_8") (pintype "unspecified+no_connect"))
    )
    (net (code "126") (name "unconnected-(U11-ALE-Pad30)") (class "Default")
      (node (ref "U11") (pin "30") (pinfunction "ALE_30") (pintype "unspecified+no_connect"))
    )
    (net (code "127") (name "unconnected-(U11-INT1#{slash}P3.3-Pad13)") (class "Default")
      (node (ref "U11") (pin "13") (pinfunction "INT1#/P3.3_13") (pintype "unspecified+no_connect"))
    )
    (net (code "128") (name "unconnected-(U11-P1.6-Pad7)") (class "Default")
      (node (ref "U11") (pin "7") (pinfunction "P1.6_7") (pintype "unspecified+no_connect"))
    )
    (net (code "129") (name "unconnected-(U11-PSEN#-Pad29)") (class "Default")
      (node (ref "U11") (pin "29") (pinfunction "PSEN#_29") (pintype "unspecified+no_connect"))
    )
    (net (code "130") (name "unconnected-(U11-RD#{slash}P3.7-Pad17)") (class "Default")
      (node (ref "U11") (pin "17") (pinfunction "RD#/P3.7_17") (pintype "unspecified+no_connect"))
    )
    (net (code "131") (name "unconnected-(U11-T0{slash}P3.4-Pad14)") (class "Default")
      (node (ref "U11") (pin "14") (pinfunction "T0/P3.4_14") (pintype "unspecified+no_connect"))
    )
    (net (code "132") (name "unconnected-(U11-T1{slash}P3.5-Pad15)") (class "Default")
      (node (ref "U11") (pin "15") (pinfunction "T1/P3.5_15") (pintype "unspecified+no_connect"))
    )
    (net (code "133") (name "unconnected-(U11-T2EX{slash}P1.1-Pad2)") (class "Default")
      (node (ref "U11") (pin "2") (pinfunction "T2EX/P1.1_2") (pintype "unspecified+no_connect"))
    )
    (net (code "134") (name "unconnected-(U11-T2{slash}P1.0-Pad1)") (class "Default")
      (node (ref "U11") (pin "1") (pinfunction "T2/P1.0_1") (pintype "unspecified+no_connect"))
    )
    (net (code "135") (name "unconnected-(U11-WR#{slash}P3.6-Pad16)") (class "Default")
      (node (ref "U11") (pin "16") (pinfunction "WR#/P3.6_16") (pintype "unspecified+no_connect"))
    )
    (net (code "136") (name "unconnected-(U15-VCC1-Pad8)") (class "Default")
      (node (ref "U15") (pin "8") (pinfunction "VCC1_8") (pintype "unspecified+no_connect"))
    )
    (net (code "137") (name "unconnected-(USB1-EH-Pad7)") (class "Default")
      (node (ref "USB1") (pin "7") (pinfunction "EH_7") (pintype "unspecified+no_connect"))
    )
  )
)
